# RX8E.net
KiCad netlist of a schematic drawn in EAGLE
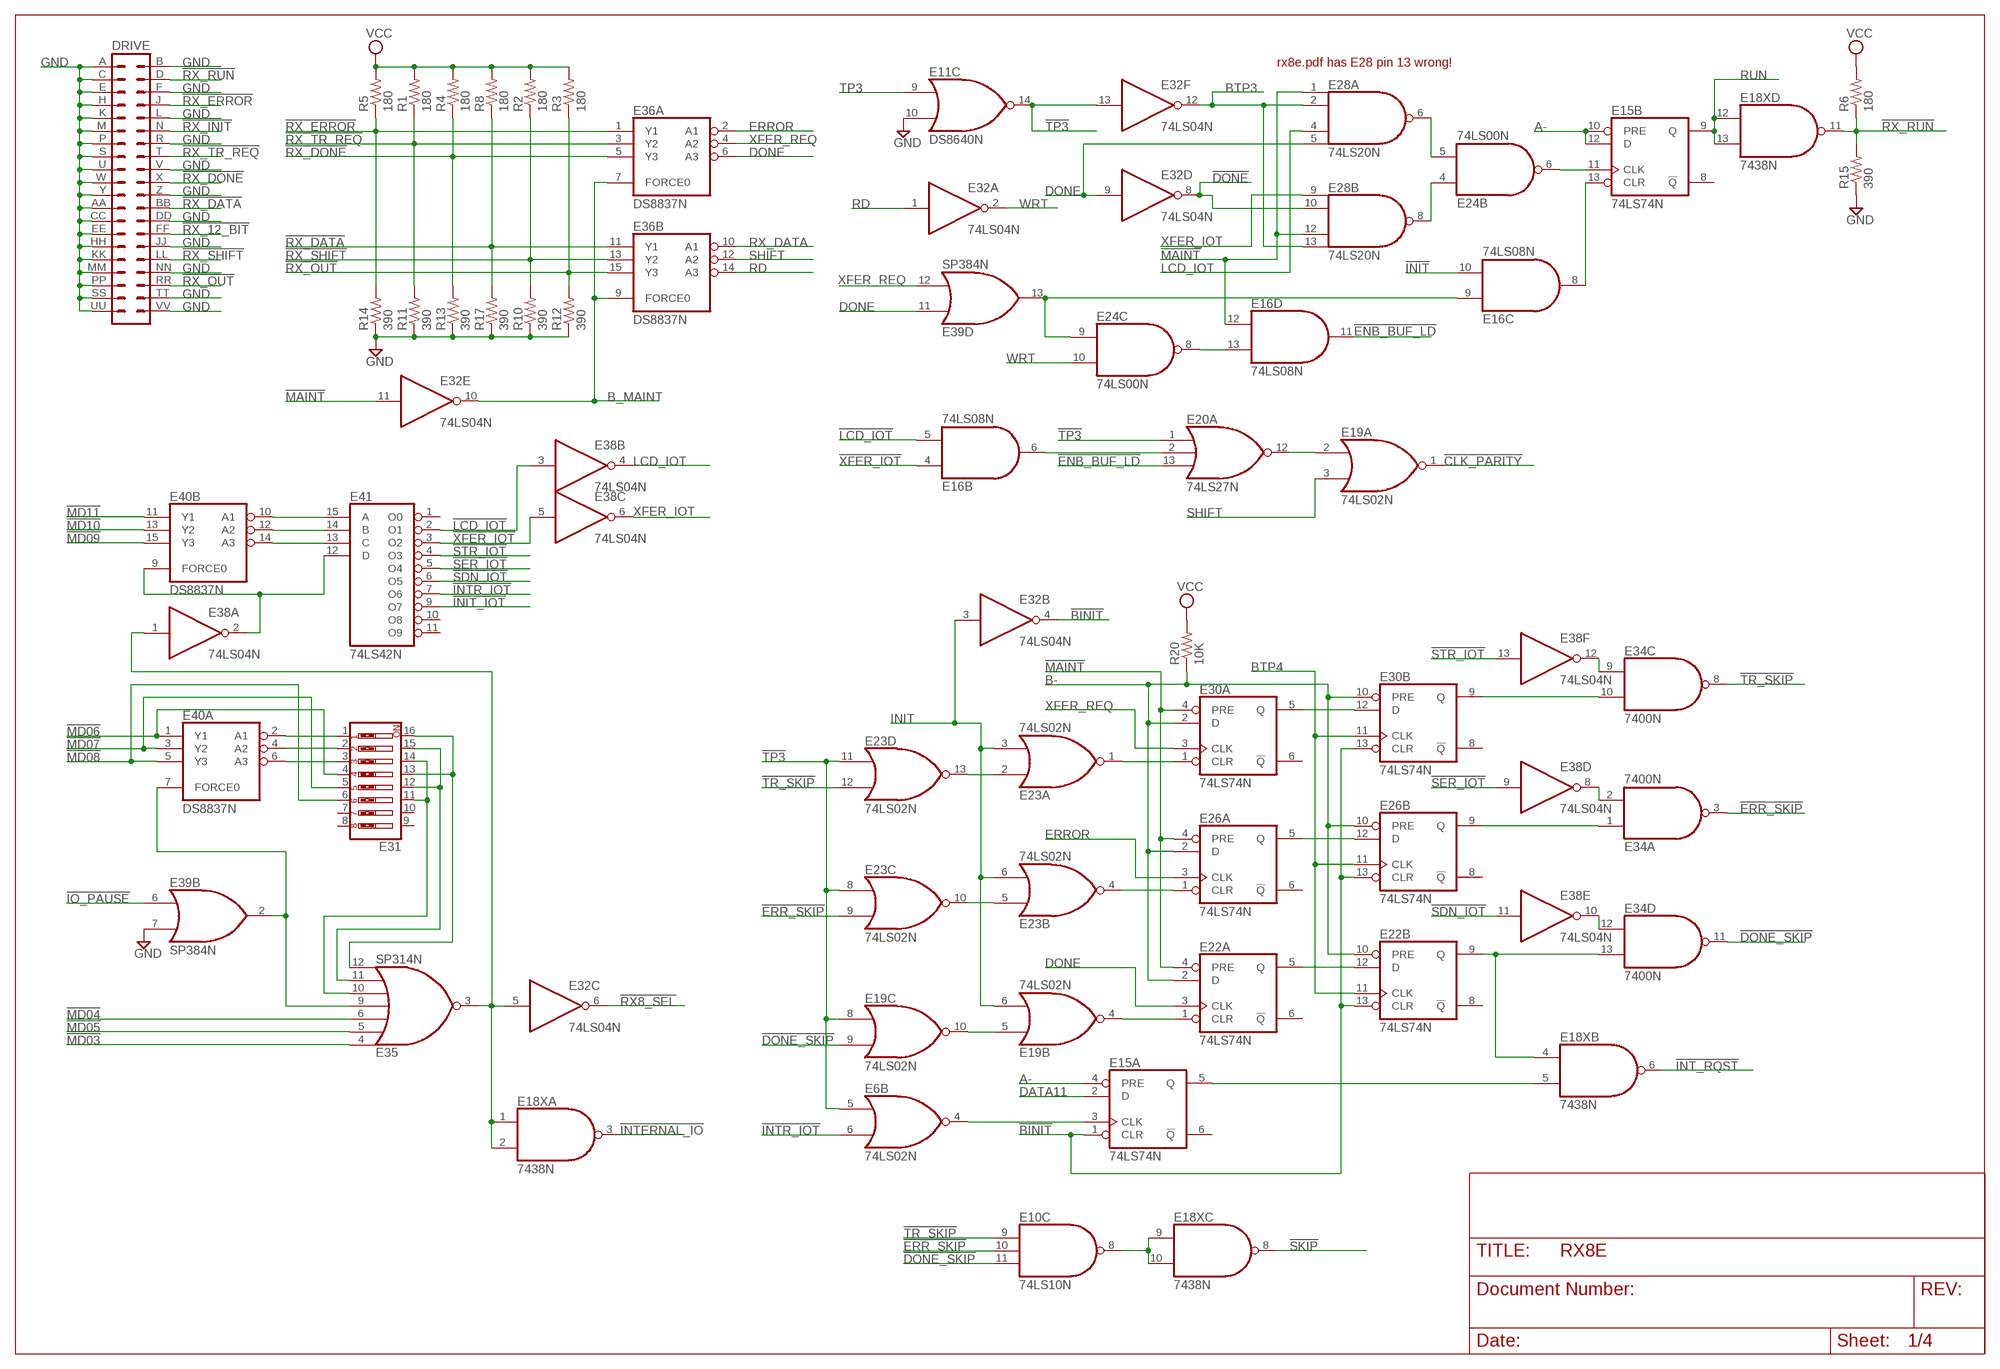
[diagram p0: schematic, sheet 1]
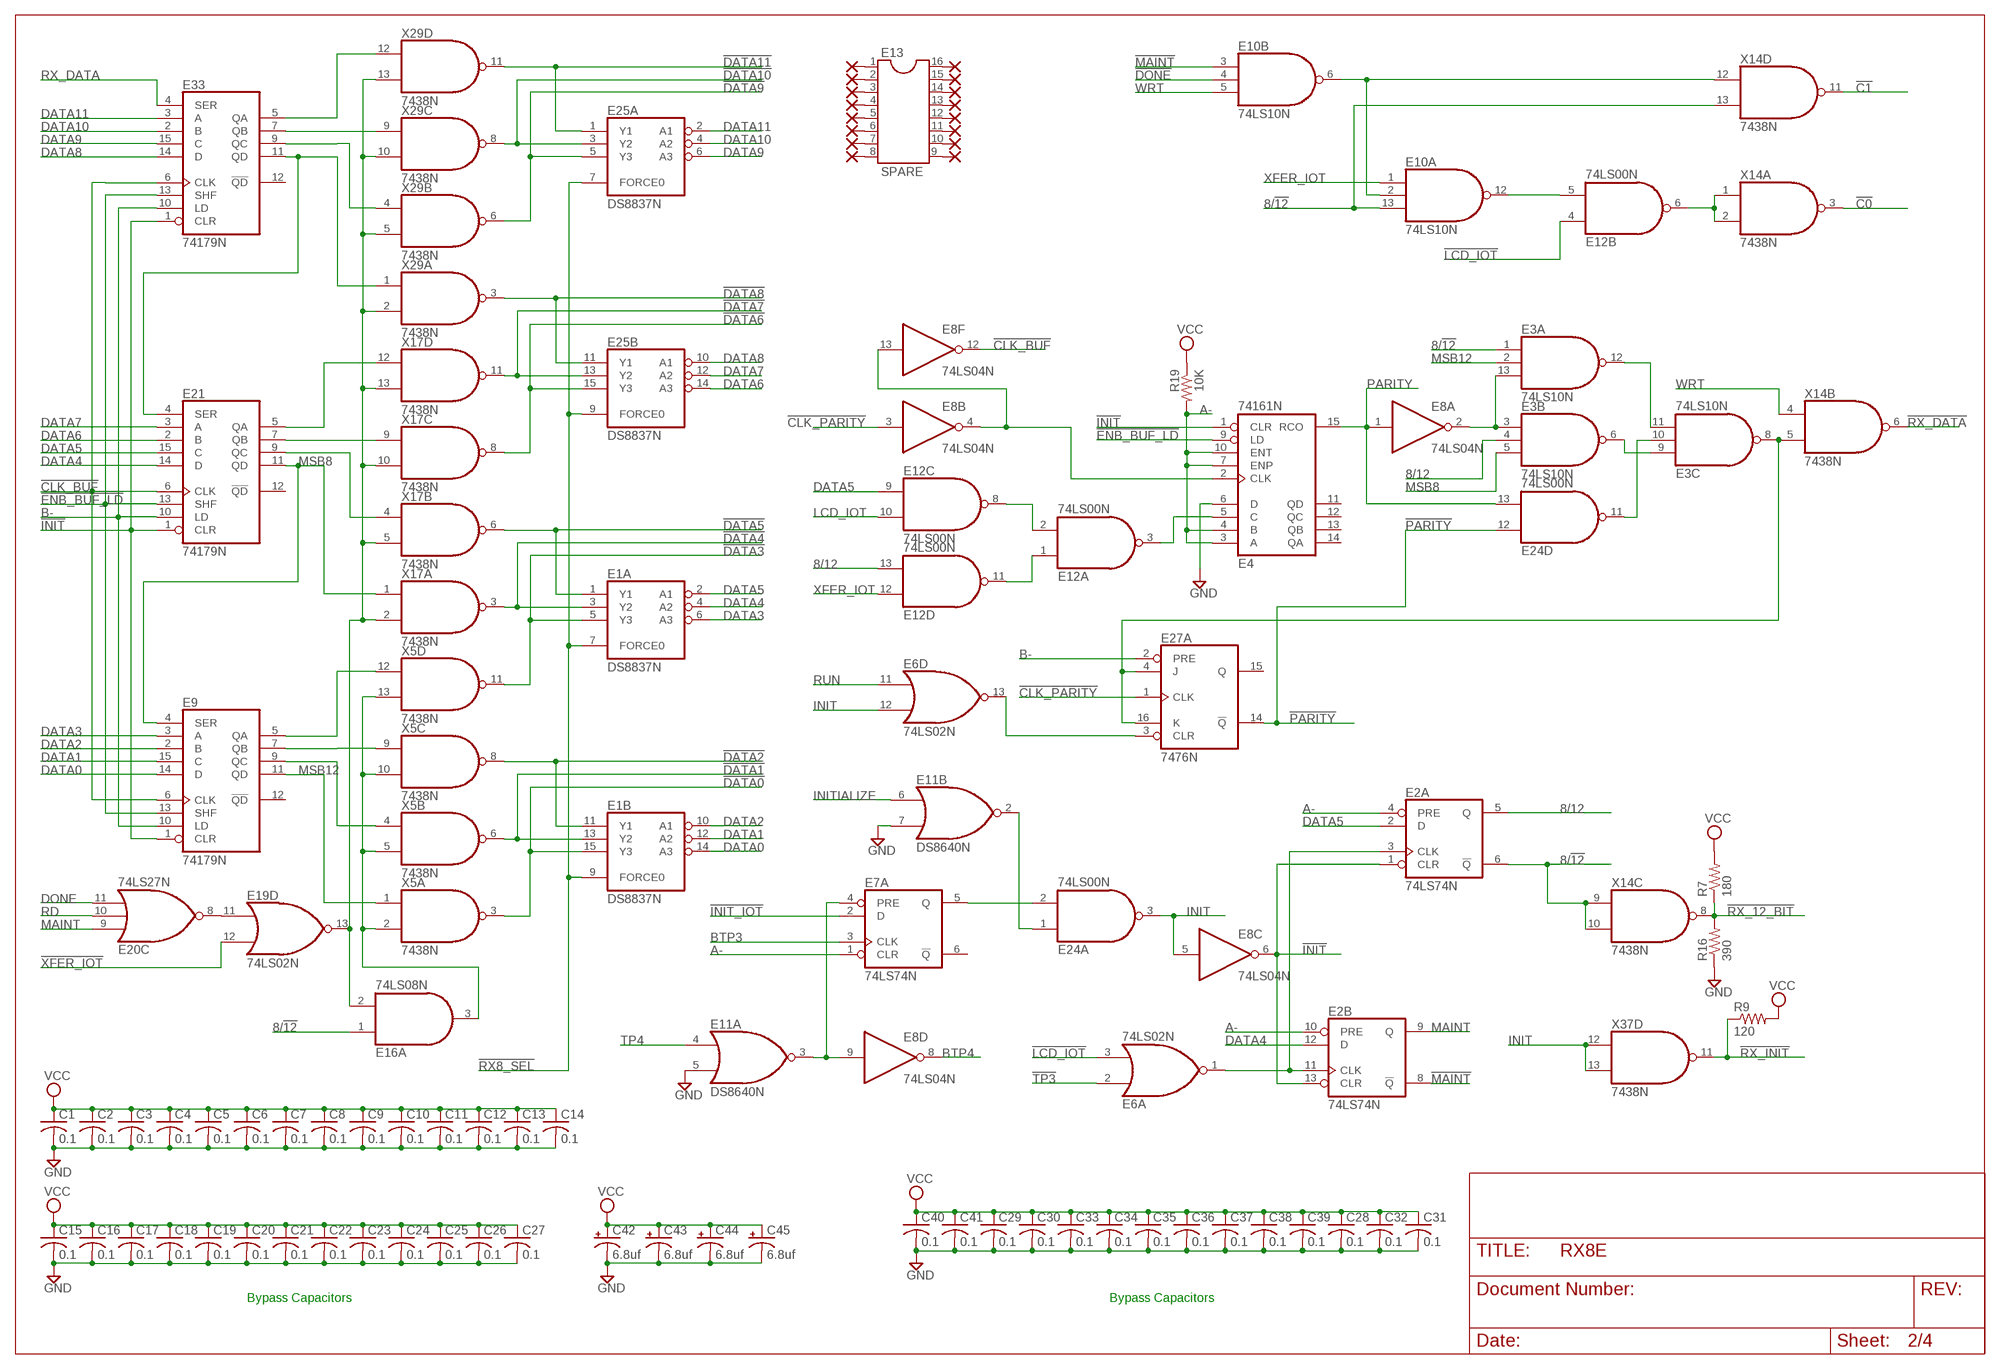
[diagram p1: schematic, sheet 2]
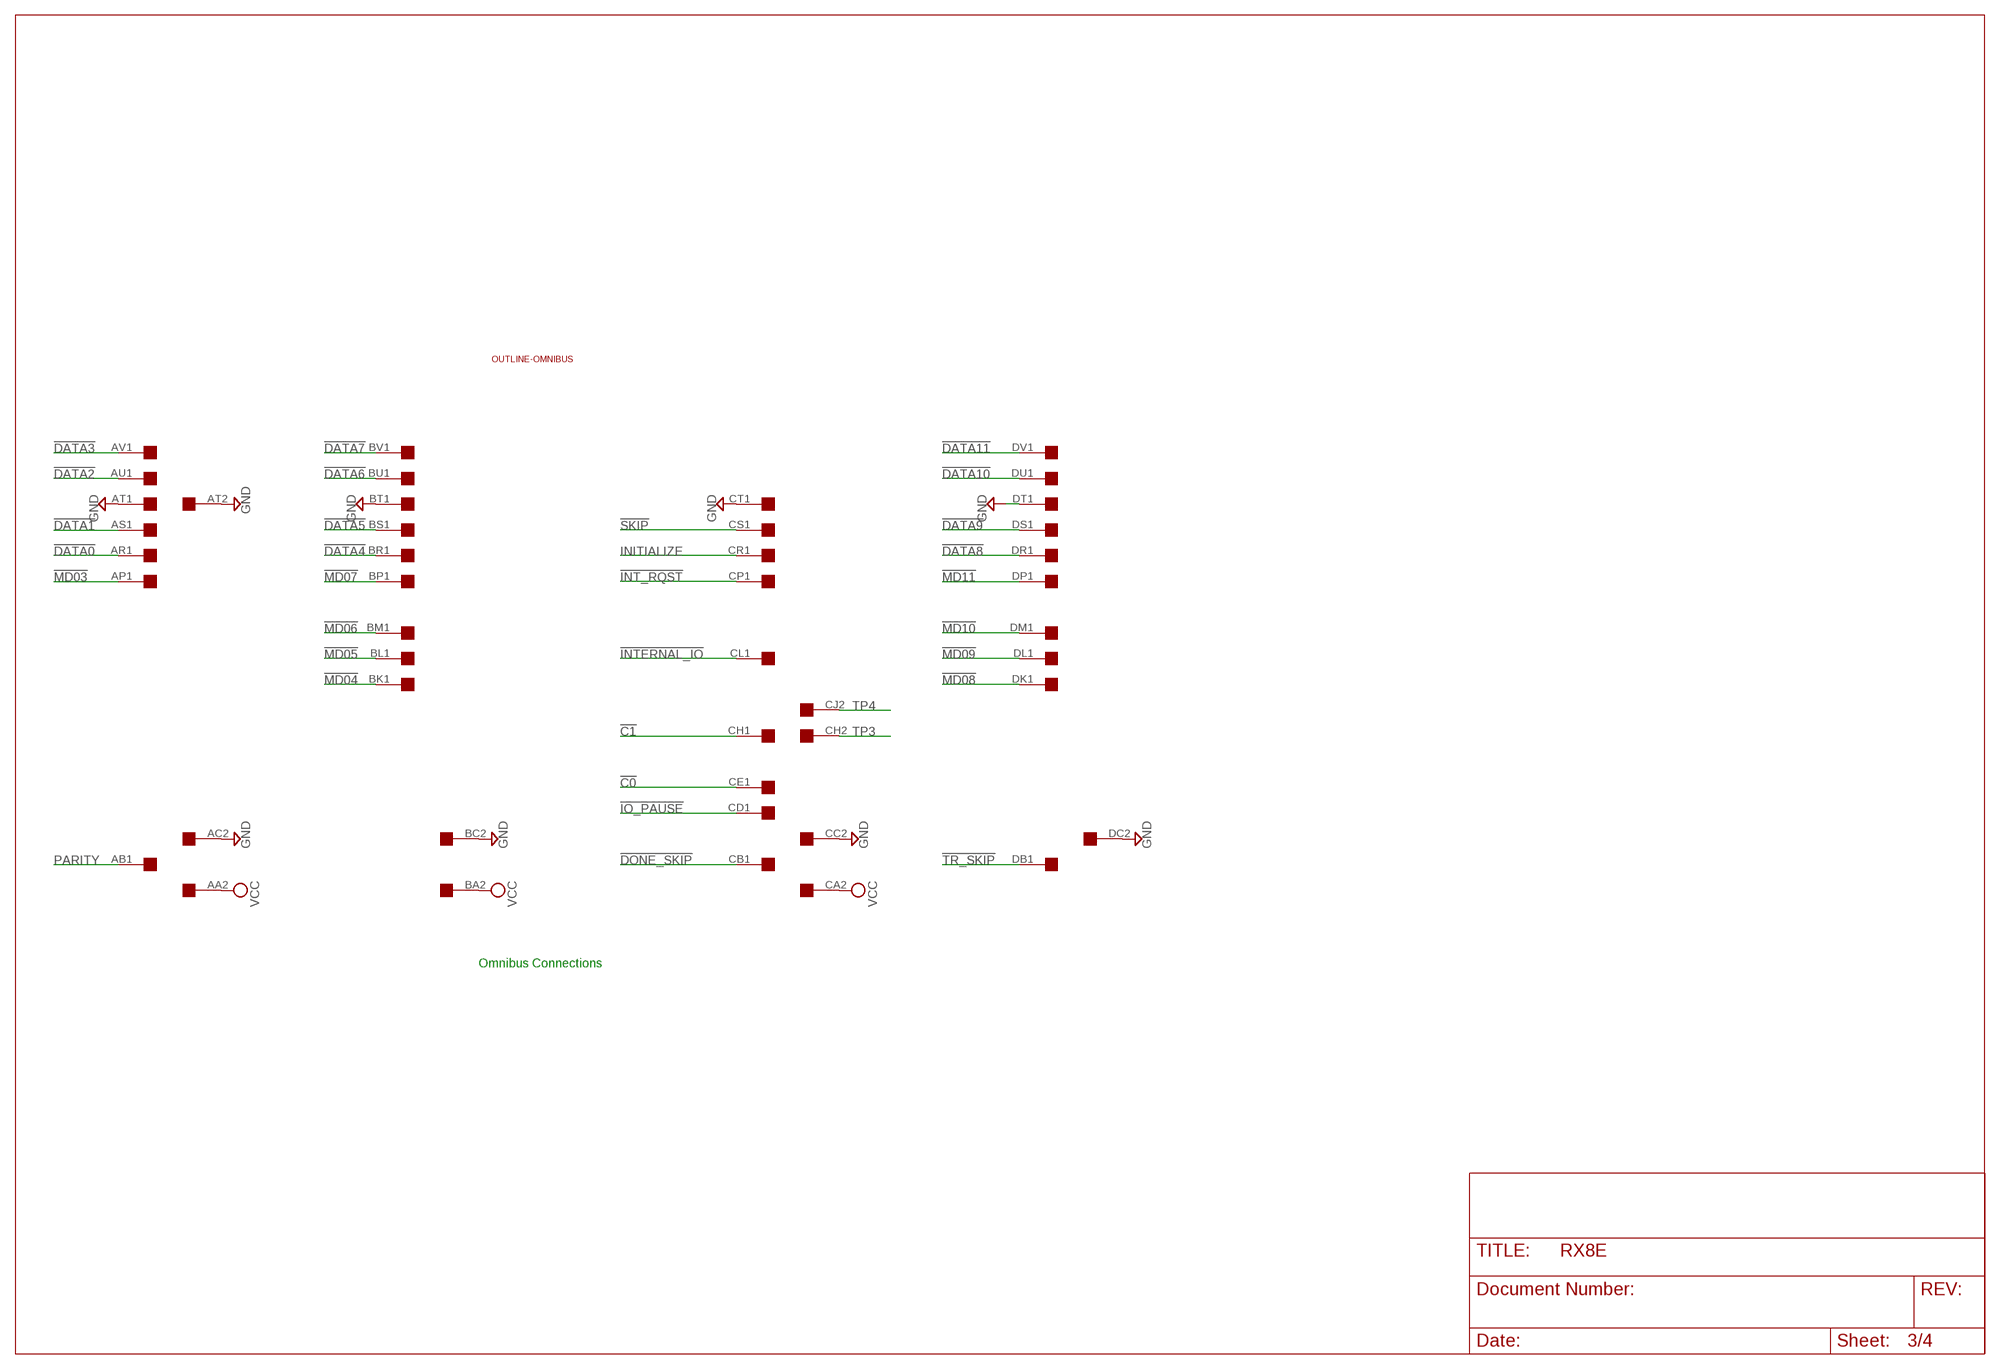
[diagram p2: schematic, sheet 3]
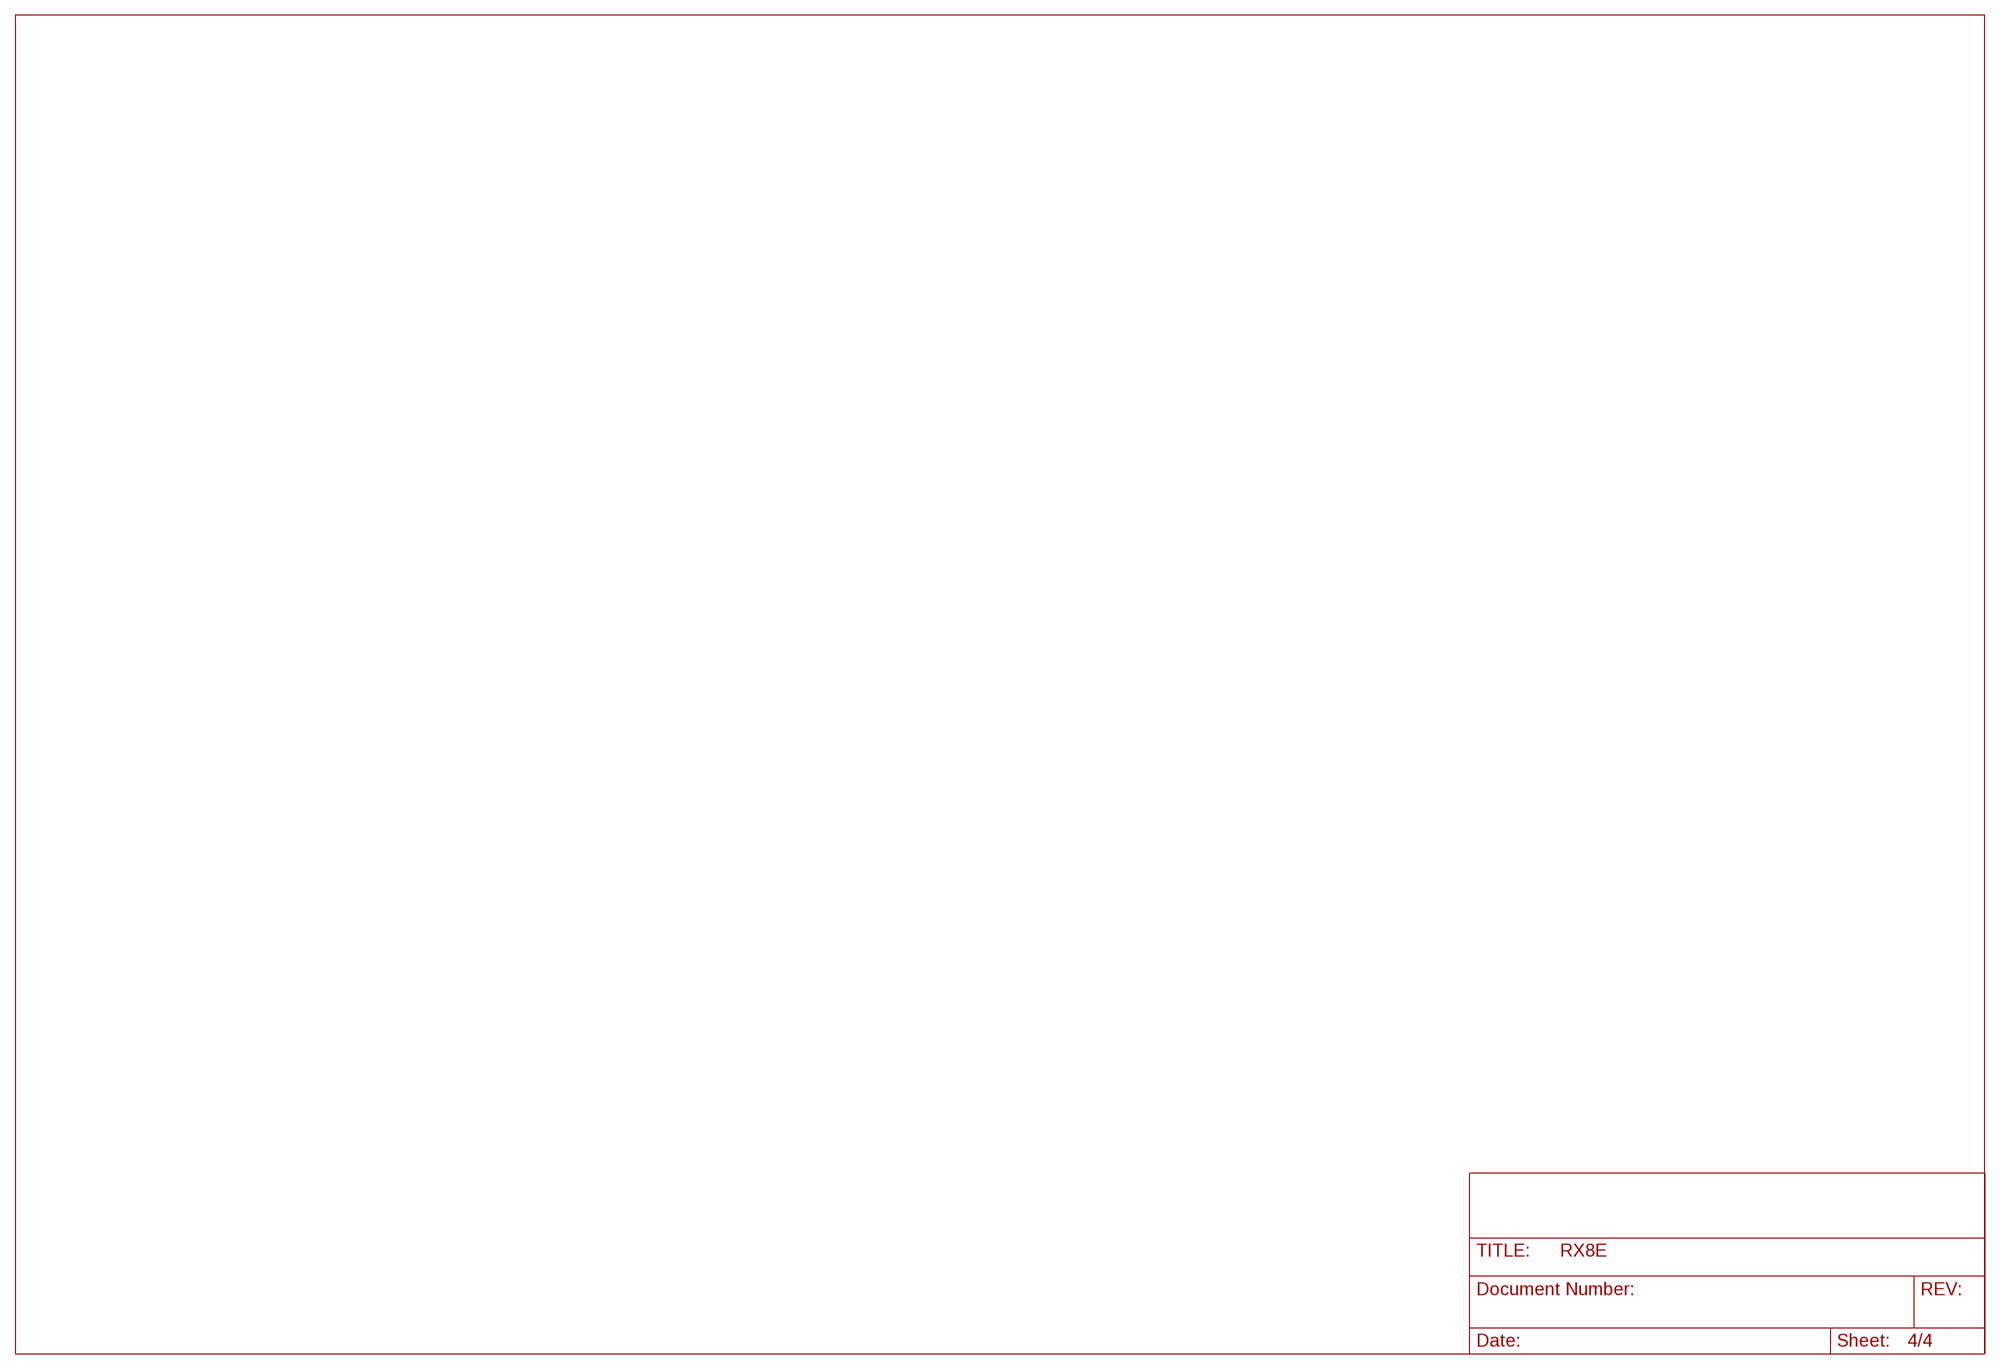
[diagram p3: schematic, sheet 4]

(export (version "E")
  (design (tool "Eeschema 10.0.6"))
  (components
    (comp (ref "U$2")
      (value "QUAD")
      (footprint "eagle-import:EDGE-CON8")
      (libsource (lib "eagle-import") (part "QUAD"))
    )
    (comp (ref "U$5")
      (value "OUTLINE-OMNIBUS")
      (footprint "eagle-import:OMNIBUS")
      (libsource (lib "eagle-import") (part "OUTLINE-OMNIBUS"))
    )
    (comp (ref "C1")
      (value "0.1")
      (footprint "eagle-import:C050-025X075")
      (libsource (lib "eagle-import") (part "C-US050-025X075"))
    )
    (comp (ref "C2")
      (value "0.1")
      (footprint "eagle-import:C050-025X075")
      (libsource (lib "eagle-import") (part "C-US050-025X075"))
    )
    (comp (ref "C3")
      (value "0.1")
      (footprint "eagle-import:C050-025X075")
      (libsource (lib "eagle-import") (part "C-US050-025X075"))
    )
    (comp (ref "C4")
      (value "0.1")
      (footprint "eagle-import:C050-025X075")
      (libsource (lib "eagle-import") (part "C-US050-025X075"))
    )
    (comp (ref "C5")
      (value "0.1")
      (footprint "eagle-import:C050-025X075")
      (libsource (lib "eagle-import") (part "C-US050-025X075"))
    )
    (comp (ref "C6")
      (value "0.1")
      (footprint "eagle-import:C050-025X075")
      (libsource (lib "eagle-import") (part "C-US050-025X075"))
    )
    (comp (ref "C7")
      (value "0.1")
      (footprint "eagle-import:C050-025X075")
      (libsource (lib "eagle-import") (part "C-US050-025X075"))
    )
    (comp (ref "C8")
      (value "0.1")
      (footprint "eagle-import:C050-025X075")
      (libsource (lib "eagle-import") (part "C-US050-025X075"))
    )
    (comp (ref "C9")
      (value "0.1")
      (footprint "eagle-import:C050-025X075")
      (libsource (lib "eagle-import") (part "C-US050-025X075"))
    )
    (comp (ref "C10")
      (value "0.1")
      (footprint "eagle-import:C050-025X075")
      (libsource (lib "eagle-import") (part "C-US050-025X075"))
    )
    (comp (ref "C11")
      (value "0.1")
      (footprint "eagle-import:C050-025X075")
      (libsource (lib "eagle-import") (part "C-US050-025X075"))
    )
    (comp (ref "C12")
      (value "0.1")
      (footprint "eagle-import:C050-025X075")
      (libsource (lib "eagle-import") (part "C-US050-025X075"))
    )
    (comp (ref "C13")
      (value "0.1")
      (footprint "eagle-import:C050-025X075")
      (libsource (lib "eagle-import") (part "C-US050-025X075"))
    )
    (comp (ref "C14")
      (value "0.1")
      (footprint "eagle-import:C050-025X075")
      (libsource (lib "eagle-import") (part "C-US050-025X075"))
    )
    (comp (ref "C15")
      (value "0.1")
      (footprint "eagle-import:C050-025X075")
      (libsource (lib "eagle-import") (part "C-US050-025X075"))
    )
    (comp (ref "C16")
      (value "0.1")
      (footprint "eagle-import:C050-025X075")
      (libsource (lib "eagle-import") (part "C-US050-025X075"))
    )
    (comp (ref "C17")
      (value "0.1")
      (footprint "eagle-import:C050-025X075")
      (libsource (lib "eagle-import") (part "C-US050-025X075"))
    )
    (comp (ref "C18")
      (value "0.1")
      (footprint "eagle-import:C050-025X075")
      (libsource (lib "eagle-import") (part "C-US050-025X075"))
    )
    (comp (ref "C19")
      (value "0.1")
      (footprint "eagle-import:C050-025X075")
      (libsource (lib "eagle-import") (part "C-US050-025X075"))
    )
    (comp (ref "C20")
      (value "0.1")
      (footprint "eagle-import:C050-025X075")
      (libsource (lib "eagle-import") (part "C-US050-025X075"))
    )
    (comp (ref "C21")
      (value "0.1")
      (footprint "eagle-import:C050-025X075")
      (libsource (lib "eagle-import") (part "C-US050-025X075"))
    )
    (comp (ref "C22")
      (value "0.1")
      (footprint "eagle-import:C050-025X075")
      (libsource (lib "eagle-import") (part "C-US050-025X075"))
    )
    (comp (ref "C23")
      (value "0.1")
      (footprint "eagle-import:C050-025X075")
      (libsource (lib "eagle-import") (part "C-US050-025X075"))
    )
    (comp (ref "C24")
      (value "0.1")
      (footprint "eagle-import:C050-025X075")
      (libsource (lib "eagle-import") (part "C-US050-025X075"))
    )
    (comp (ref "C25")
      (value "0.1")
      (footprint "eagle-import:C050-025X075")
      (libsource (lib "eagle-import") (part "C-US050-025X075"))
    )
    (comp (ref "C26")
      (value "0.1")
      (footprint "eagle-import:C050-025X075")
      (libsource (lib "eagle-import") (part "C-US050-025X075"))
    )
    (comp (ref "C27")
      (value "0.1")
      (footprint "eagle-import:C050-025X075")
      (libsource (lib "eagle-import") (part "C-US050-025X075"))
    )
    (comp (ref "C28")
      (value "0.1")
      (footprint "eagle-import:C050-025X075")
      (libsource (lib "eagle-import") (part "C-US050-025X075"))
    )
    (comp (ref "C29")
      (value "0.1")
      (footprint "eagle-import:C050-025X075")
      (libsource (lib "eagle-import") (part "C-US050-025X075"))
    )
    (comp (ref "C30")
      (value "0.1")
      (footprint "eagle-import:C050-025X075")
      (libsource (lib "eagle-import") (part "C-US050-025X075"))
    )
    (comp (ref "C31")
      (value "0.1")
      (footprint "eagle-import:C050-025X075")
      (libsource (lib "eagle-import") (part "C-US050-025X075"))
    )
    (comp (ref "C32")
      (value "0.1")
      (footprint "eagle-import:C050-025X075")
      (libsource (lib "eagle-import") (part "C-US050-025X075"))
    )
    (comp (ref "C33")
      (value "0.1")
      (footprint "eagle-import:C050-025X075")
      (libsource (lib "eagle-import") (part "C-US050-025X075"))
    )
    (comp (ref "C34")
      (value "0.1")
      (footprint "eagle-import:C050-025X075")
      (libsource (lib "eagle-import") (part "C-US050-025X075"))
    )
    (comp (ref "C35")
      (value "0.1")
      (footprint "eagle-import:C050-025X075")
      (libsource (lib "eagle-import") (part "C-US050-025X075"))
    )
    (comp (ref "C36")
      (value "0.1")
      (footprint "eagle-import:C050-025X075")
      (libsource (lib "eagle-import") (part "C-US050-025X075"))
    )
    (comp (ref "C37")
      (value "0.1")
      (footprint "eagle-import:C050-025X075")
      (libsource (lib "eagle-import") (part "C-US050-025X075"))
    )
    (comp (ref "C38")
      (value "0.1")
      (footprint "eagle-import:C050-025X075")
      (libsource (lib "eagle-import") (part "C-US050-025X075"))
    )
    (comp (ref "C39")
      (value "0.1")
      (footprint "eagle-import:C050-025X075")
      (libsource (lib "eagle-import") (part "C-US050-025X075"))
    )
    (comp (ref "C40")
      (value "0.1")
      (footprint "eagle-import:C050-025X075")
      (libsource (lib "eagle-import") (part "C-US050-025X075"))
    )
    (comp (ref "C41")
      (value "0.1")
      (footprint "eagle-import:C050-025X075")
      (libsource (lib "eagle-import") (part "C-US050-025X075"))
    )
    (comp (ref "C42")
      (value "6.8uf")
      (footprint "eagle-import:E22-6")
      (libsource (lib "eagle-import") (part "CPOL-USE22-6AXIAL"))
    )
    (comp (ref "C43")
      (value "6.8uf")
      (footprint "eagle-import:E22-6")
      (libsource (lib "eagle-import") (part "CPOL-USE22-6AXIAL"))
    )
    (comp (ref "C44")
      (value "6.8uf")
      (footprint "eagle-import:E22-6")
      (libsource (lib "eagle-import") (part "CPOL-USE22-6AXIAL"))
    )
    (comp (ref "C45")
      (value "6.8uf")
      (footprint "eagle-import:E22-6")
      (libsource (lib "eagle-import") (part "CPOL-USE22-6AXIAL"))
    )
    (comp (ref "E1")
      (value "DS8837N")
      (footprint "eagle-import:DIL16")
      (libsource (lib "eagle-import") (part "DS8837N"))
    )
    (comp (ref "E2")
      (value "74LS74N")
      (footprint "eagle-import:DIL14")
      (libsource (lib "eagle-import") (part "7474NLS"))
    )
    (comp (ref "E3")
      (value "74LS10N")
      (footprint "eagle-import:DIL14")
      (libsource (lib "eagle-import") (part "7410NLS"))
    )
    (comp (ref "E4")
      (value "74161N")
      (footprint "eagle-import:DIL16")
      (libsource (lib "eagle-import") (part "74161N"))
    )
    (comp (ref "E6")
      (value "74LS02N")
      (footprint "eagle-import:DIL14")
      (libsource (lib "eagle-import") (part "7402NLS"))
    )
    (comp (ref "E7")
      (value "74LS74N")
      (footprint "eagle-import:DIL14")
      (libsource (lib "eagle-import") (part "7474NLS"))
    )
    (comp (ref "E8")
      (value "74LS04N")
      (footprint "eagle-import:DIL14")
      (libsource (lib "eagle-import") (part "7404NLS"))
    )
    (comp (ref "E9")
      (value "74179N")
      (footprint "eagle-import:DIL16")
      (libsource (lib "eagle-import") (part "74179N"))
    )
    (comp (ref "E10")
      (value "74LS10N")
      (footprint "eagle-import:DIL14")
      (libsource (lib "eagle-import") (part "7410NLS"))
    )
    (comp (ref "E11")
      (value "DS8640N")
      (footprint "eagle-import:DIL14")
      (libsource (lib "eagle-import") (part "DS8640N"))
    )
    (comp (ref "E12")
      (value "74LS00N")
      (footprint "eagle-import:DIL14")
      (libsource (lib "eagle-import") (part "7400NLS"))
    )
    (comp (ref "E13")
      (value "SPARE")
      (footprint "eagle-import:DIL16")
      (libsource (lib "eagle-import") (part "DIL16"))
    )
    (comp (ref "E16")
      (value "74LS08N")
      (footprint "eagle-import:DIL14")
      (libsource (lib "eagle-import") (part "7408NLS"))
    )
    (comp (ref "E19")
      (value "74LS02N")
      (footprint "eagle-import:DIL14")
      (libsource (lib "eagle-import") (part "7402NLS"))
    )
    (comp (ref "E20")
      (value "74LS27N")
      (footprint "eagle-import:DIL14")
      (libsource (lib "eagle-import") (part "7427NLS"))
    )
    (comp (ref "E21")
      (value "74179N")
      (footprint "eagle-import:DIL16")
      (libsource (lib "eagle-import") (part "74179N"))
    )
    (comp (ref "E24")
      (value "74LS00N")
      (footprint "eagle-import:DIL14")
      (libsource (lib "eagle-import") (part "7400NLS"))
    )
    (comp (ref "E25")
      (value "DS8837N")
      (footprint "eagle-import:DIL16")
      (libsource (lib "eagle-import") (part "DS8837N"))
    )
    (comp (ref "E27")
      (value "7476N")
      (footprint "eagle-import:DIL16")
      (libsource (lib "eagle-import") (part "7476N"))
    )
    (comp (ref "E33")
      (value "74179N")
      (footprint "eagle-import:DIL16")
      (libsource (lib "eagle-import") (part "74179N"))
    )
    (comp (ref "PAD10")
      (value "1,6/0,8")
      (footprint "eagle-import:1,6_0,8")
      (libsource (lib "eagle-import") (part "1,6/0,8"))
    )
    (comp (ref "PAD11")
      (value "1,6/0,8")
      (footprint "eagle-import:1,6_0,8")
      (libsource (lib "eagle-import") (part "1,6/0,8"))
    )
    (comp (ref "PAD12")
      (value "1,6/0,8")
      (footprint "eagle-import:1,6_0,8")
      (libsource (lib "eagle-import") (part "1,6/0,8"))
    )
    (comp (ref "PAD13")
      (value "1,6/0,8")
      (footprint "eagle-import:1,6_0,8")
      (libsource (lib "eagle-import") (part "1,6/0,8"))
    )
    (comp (ref "PAD14")
      (value "1,6/0,8")
      (footprint "eagle-import:1,6_0,8")
      (libsource (lib "eagle-import") (part "1,6/0,8"))
    )
    (comp (ref "PAD15")
      (value "1,6/0,8")
      (footprint "eagle-import:1,6_0,8")
      (libsource (lib "eagle-import") (part "1,6/0,8"))
    )
    (comp (ref "PAD16")
      (value "1,6/0,8")
      (footprint "eagle-import:1,6_0,8")
      (libsource (lib "eagle-import") (part "1,6/0,8"))
    )
    (comp (ref "PAD17")
      (value "1,6/0,8")
      (footprint "eagle-import:1,6_0,8")
      (libsource (lib "eagle-import") (part "1,6/0,8"))
    )
    (comp (ref "PAD20")
      (value "1,6/0,8")
      (footprint "eagle-import:1,6_0,8")
      (libsource (lib "eagle-import") (part "1,6/0,8"))
    )
    (comp (ref "PAD21")
      (value "1,6/0,8")
      (footprint "eagle-import:1,6_0,8")
      (libsource (lib "eagle-import") (part "1,6/0,8"))
    )
    (comp (ref "PAD22")
      (value "1,6/0,8")
      (footprint "eagle-import:1,6_0,8")
      (libsource (lib "eagle-import") (part "1,6/0,8"))
    )
    (comp (ref "PAD23")
      (value "1,6/0,8")
      (footprint "eagle-import:1,6_0,8")
      (libsource (lib "eagle-import") (part "1,6/0,8"))
    )
    (comp (ref "PAD24")
      (value "1,6/0,8")
      (footprint "eagle-import:1,6_0,8")
      (libsource (lib "eagle-import") (part "1,6/0,8"))
    )
    (comp (ref "PAD25")
      (value "1,6/0,8")
      (footprint "eagle-import:1,6_0,8")
      (libsource (lib "eagle-import") (part "1,6/0,8"))
    )
    (comp (ref "PAD26")
      (value "1,6/0,8")
      (footprint "eagle-import:1,6_0,8")
      (libsource (lib "eagle-import") (part "1,6/0,8"))
    )
    (comp (ref "PAD27")
      (value "1,6/0,8")
      (footprint "eagle-import:1,6_0,8")
      (libsource (lib "eagle-import") (part "1,6/0,8"))
    )
    (comp (ref "R7")
      (value "180")
      (footprint "eagle-import:0207_10")
      (libsource (lib "eagle-import") (part "R-US_0207/10"))
    )
    (comp (ref "R9")
      (value "120")
      (footprint "eagle-import:0207_10")
      (libsource (lib "eagle-import") (part "R-US_0207/10"))
    )
    (comp (ref "R16")
      (value "390")
      (footprint "eagle-import:0207_10")
      (libsource (lib "eagle-import") (part "R-US_0207/10"))
    )
    (comp (ref "R19")
      (value "10K")
      (footprint "eagle-import:0207_10")
      (libsource (lib "eagle-import") (part "R-US_0207/10"))
    )
    (comp (ref "X5")
      (value "7438N")
      (footprint "eagle-import:DIL14")
      (libsource (lib "eagle-import") (part "7403NS"))
    )
    (comp (ref "X14")
      (value "7438N")
      (footprint "eagle-import:DIL14")
      (libsource (lib "eagle-import") (part "7403NS"))
    )
    (comp (ref "X17")
      (value "7438N")
      (footprint "eagle-import:DIL14")
      (libsource (lib "eagle-import") (part "7403NS"))
    )
    (comp (ref "X29")
      (value "7438N")
      (footprint "eagle-import:DIL14")
      (libsource (lib "eagle-import") (part "7403NS"))
    )
    (comp (ref "X37")
      (value "7438N")
      (footprint "eagle-import:DIL14")
      (libsource (lib "eagle-import") (part "7403NS"))
    )
    (comp (ref "DRIVE")
      (value "DEC40PINH")
      (footprint "eagle-import:DEC40PINH")
      (libsource (lib "eagle-import") (part "DEC40PINH"))
    )
    (comp (ref "E15")
      (value "74LS74N")
      (footprint "eagle-import:DIL14")
      (libsource (lib "eagle-import") (part "7474NLS"))
    )
    (comp (ref "E18X")
      (value "7438N")
      (footprint "eagle-import:DIL14")
      (libsource (lib "eagle-import") (part "7403NS"))
    )
    (comp (ref "E22")
      (value "74LS74N")
      (footprint "eagle-import:DIL14")
      (libsource (lib "eagle-import") (part "7474NLS"))
    )
    (comp (ref "E23")
      (value "74LS02N")
      (footprint "eagle-import:DIL14")
      (libsource (lib "eagle-import") (part "7402NLS"))
    )
    (comp (ref "E26")
      (value "74LS74N")
      (footprint "eagle-import:DIL14")
      (libsource (lib "eagle-import") (part "7474NLS"))
    )
    (comp (ref "E28")
      (value "74LS20N")
      (footprint "eagle-import:DIL14")
      (libsource (lib "eagle-import") (part "7420NLS"))
    )
    (comp (ref "E30")
      (value "74LS74N")
      (footprint "eagle-import:DIL14")
      (libsource (lib "eagle-import") (part "7474NLS"))
    )
    (comp (ref "E31")
      (value "SW_DIP-8")
      (footprint "eagle-import:EDG-08")
      (libsource (lib "eagle-import") (part "SW_DIP-8"))
    )
    (comp (ref "E32")
      (value "74LS04N")
      (footprint "eagle-import:DIL14")
      (libsource (lib "eagle-import") (part "7404NLS"))
    )
    (comp (ref "E34")
      (value "7400N")
      (footprint "eagle-import:DIL14")
      (libsource (lib "eagle-import") (part "7400N"))
    )
    (comp (ref "E35")
      (value "SP314N")
      (footprint "eagle-import:DIL14")
      (libsource (lib "eagle-import") (part "SP314N"))
    )
    (comp (ref "E36")
      (value "DS8837N")
      (footprint "eagle-import:DIL16")
      (libsource (lib "eagle-import") (part "DS8837N"))
    )
    (comp (ref "E38")
      (value "74LS04N")
      (footprint "eagle-import:DIL14")
      (libsource (lib "eagle-import") (part "7404NLS"))
    )
    (comp (ref "E39")
      (value "SP384N")
      (footprint "eagle-import:DIL14")
      (libsource (lib "eagle-import") (part "SP384N"))
    )
    (comp (ref "E40")
      (value "DS8837N")
      (footprint "eagle-import:DIL16")
      (libsource (lib "eagle-import") (part "DS8837N"))
    )
    (comp (ref "E41")
      (value "74LS42N")
      (footprint "eagle-import:DIL16")
      (libsource (lib "eagle-import") (part "7442NLS"))
    )
    (comp (ref "R1")
      (value "180")
      (footprint "eagle-import:0207_10")
      (libsource (lib "eagle-import") (part "R-US_0207/10"))
    )
    (comp (ref "R2")
      (value "180")
      (footprint "eagle-import:0207_10")
      (libsource (lib "eagle-import") (part "R-US_0207/10"))
    )
    (comp (ref "R3")
      (value "180")
      (footprint "eagle-import:0207_10")
      (libsource (lib "eagle-import") (part "R-US_0207/10"))
    )
    (comp (ref "R4")
      (value "180")
      (footprint "eagle-import:0207_10")
      (libsource (lib "eagle-import") (part "R-US_0207/10"))
    )
    (comp (ref "R5")
      (value "180")
      (footprint "eagle-import:0207_10")
      (libsource (lib "eagle-import") (part "R-US_0207/10"))
    )
    (comp (ref "R6")
      (value "180")
      (footprint "eagle-import:0207_10")
      (libsource (lib "eagle-import") (part "R-US_0207/10"))
    )
    (comp (ref "R8")
      (value "180")
      (footprint "eagle-import:0207_10")
      (libsource (lib "eagle-import") (part "R-US_0207/10"))
    )
    (comp (ref "R10")
      (value "390")
      (footprint "eagle-import:0207_10")
      (libsource (lib "eagle-import") (part "R-US_0207/10"))
    )
    (comp (ref "R11")
      (value "390")
      (footprint "eagle-import:0207_10")
      (libsource (lib "eagle-import") (part "R-US_0207/10"))
    )
    (comp (ref "R12")
      (value "390")
      (footprint "eagle-import:0207_10")
      (libsource (lib "eagle-import") (part "R-US_0207/10"))
    )
    (comp (ref "R13")
      (value "390")
      (footprint "eagle-import:0207_10")
      (libsource (lib "eagle-import") (part "R-US_0207/10"))
    )
    (comp (ref "R14")
      (value "390")
      (footprint "eagle-import:0207_10")
      (libsource (lib "eagle-import") (part "R-US_0207/10"))
    )
    (comp (ref "R15")
      (value "390")
      (footprint "eagle-import:0207_10")
      (libsource (lib "eagle-import") (part "R-US_0207/10"))
    )
    (comp (ref "R17")
      (value "390")
      (footprint "eagle-import:0207_10")
      (libsource (lib "eagle-import") (part "R-US_0207/10"))
    )
    (comp (ref "R20")
      (value "10K")
      (footprint "eagle-import:0207_10")
      (libsource (lib "eagle-import") (part "R-US_0207/10"))
    )
  )
  (nets
    (net (code "1") (name "8{slash}12") (class "Default")
      (node (ref "E12") (pin "13") (pinfunction "I1_13") (pintype "input"))
      (node (ref "E2") (pin "5") (pinfunction "Q_5") (pintype "output"))
      (node (ref "E3") (pin "4") (pinfunction "I1_4") (pintype "input"))
    )
    (net (code "2") (name "8{slash}~{12}") (class "Default")
      (node (ref "E10") (pin "13") (pinfunction "I2_13") (pintype "input"))
      (node (ref "E16") (pin "1") (pinfunction "I0_1") (pintype "input"))
      (node (ref "E2") (pin "6") (pinfunction "~{Q}_6") (pintype "output"))
      (node (ref "E3") (pin "1") (pinfunction "I0_1") (pintype "input"))
      (node (ref "X14") (pin "10") (pinfunction "I1_10") (pintype "input"))
      (node (ref "X14") (pin "13") (pinfunction "I1_13") (pintype "input"))
      (node (ref "X14") (pin "9") (pinfunction "I0_9") (pintype "input"))
    )
    (net (code "3") (name "A-") (class "Default")
      (node (ref "E15") (pin "10") (pinfunction "PRE_10") (pintype "input"))
      (node (ref "E15") (pin "12") (pinfunction "D_12") (pintype "input"))
      (node (ref "E15") (pin "4") (pinfunction "PRE_4") (pintype "input"))
      (node (ref "E2") (pin "10") (pinfunction "PRE_10") (pintype "input"))
      (node (ref "E2") (pin "4") (pinfunction "PRE_4") (pintype "input"))
      (node (ref "E4") (pin "10") (pinfunction "ENT_10") (pintype "input"))
      (node (ref "E4") (pin "3") (pinfunction "A_3") (pintype "input"))
      (node (ref "E4") (pin "4") (pinfunction "B_4") (pintype "input"))
      (node (ref "E4") (pin "7") (pinfunction "ENP_7") (pintype "input"))
      (node (ref "E7") (pin "1") (pinfunction "CLR_1") (pintype "input"))
      (node (ref "R19") (pin "2") (pinfunction "2_2") (pintype "passive"))
    )
    (net (code "4") (name "B-") (class "Default")
      (node (ref "E21") (pin "10") (pinfunction "LD_10") (pintype "input"))
      (node (ref "E22") (pin "10") (pinfunction "PRE_10") (pintype "input"))
      (node (ref "E22") (pin "2") (pinfunction "D_2") (pintype "input"))
      (node (ref "E26") (pin "10") (pinfunction "PRE_10") (pintype "input"))
      (node (ref "E26") (pin "2") (pinfunction "D_2") (pintype "input"))
      (node (ref "E27") (pin "2") (pinfunction "PRE_2") (pintype "input"))
      (node (ref "E30") (pin "10") (pinfunction "PRE_10") (pintype "input"))
      (node (ref "E30") (pin "2") (pinfunction "D_2") (pintype "input"))
      (node (ref "E33") (pin "10") (pinfunction "LD_10") (pintype "input"))
      (node (ref "E9") (pin "10") (pinfunction "LD_10") (pintype "input"))
      (node (ref "R20") (pin "1") (pinfunction "1_1") (pintype "passive"))
    )
    (net (code "5") (name "BTP3") (class "Default")
      (node (ref "E28") (pin "13") (pinfunction "I3_13") (pintype "input"))
      (node (ref "E28") (pin "2") (pinfunction "I1_2") (pintype "input"))
      (node (ref "E32") (pin "12") (pinfunction "O_12") (pintype "output"))
      (node (ref "E7") (pin "3") (pinfunction "CLK_3") (pintype "input"))
    )
    (net (code "6") (name "BTP4") (class "Default")
      (node (ref "E22") (pin "11") (pinfunction "CLK_11") (pintype "input"))
      (node (ref "E26") (pin "11") (pinfunction "CLK_11") (pintype "input"))
      (node (ref "E30") (pin "11") (pinfunction "CLK_11") (pintype "input"))
      (node (ref "E8") (pin "8") (pinfunction "O_8") (pintype "output"))
    )
    (net (code "7") (name "B_MAINT") (class "Default")
      (node (ref "E32") (pin "10") (pinfunction "O_10") (pintype "output"))
      (node (ref "E36") (pin "7") (pinfunction "FORCE0_7") (pintype "input"))
      (node (ref "E36") (pin "9") (pinfunction "FORCE0_9") (pintype "input"))
    )
    (net (code "8") (name "DATA0") (class "Default")
      (node (ref "E1") (pin "14") (pinfunction "A3_14") (pintype "output"))
      (node (ref "E9") (pin "14") (pinfunction "D_14") (pintype "input"))
    )
    (net (code "9") (name "DATA1") (class "Default")
      (node (ref "E1") (pin "12") (pinfunction "A2_12") (pintype "output"))
      (node (ref "E9") (pin "15") (pinfunction "C_15") (pintype "input"))
    )
    (net (code "10") (name "DATA2") (class "Default")
      (node (ref "E1") (pin "10") (pinfunction "A1_10") (pintype "output"))
      (node (ref "E9") (pin "2") (pinfunction "B_2") (pintype "input"))
    )
    (net (code "11") (name "DATA3") (class "Default")
      (node (ref "E1") (pin "6") (pinfunction "A3_6") (pintype "output"))
      (node (ref "E9") (pin "3") (pinfunction "A_3") (pintype "input"))
    )
    (net (code "12") (name "DATA4") (class "Default")
      (node (ref "E1") (pin "4") (pinfunction "A2_4") (pintype "output"))
      (node (ref "E2") (pin "12") (pinfunction "D_12") (pintype "input"))
      (node (ref "E21") (pin "14") (pinfunction "D_14") (pintype "input"))
    )
    (net (code "13") (name "DATA5") (class "Default")
      (node (ref "E1") (pin "2") (pinfunction "A1_2") (pintype "output"))
      (node (ref "E12") (pin "9") (pinfunction "I0_9") (pintype "input"))
      (node (ref "E2") (pin "2") (pinfunction "D_2") (pintype "input"))
      (node (ref "E21") (pin "15") (pinfunction "C_15") (pintype "input"))
    )
    (net (code "14") (name "DATA6") (class "Default")
      (node (ref "E21") (pin "2") (pinfunction "B_2") (pintype "input"))
      (node (ref "E25") (pin "14") (pinfunction "A3_14") (pintype "output"))
    )
    (net (code "15") (name "DATA7") (class "Default")
      (node (ref "E21") (pin "3") (pinfunction "A_3") (pintype "input"))
      (node (ref "E25") (pin "12") (pinfunction "A2_12") (pintype "output"))
    )
    (net (code "16") (name "DATA8") (class "Default")
      (node (ref "E25") (pin "10") (pinfunction "A1_10") (pintype "output"))
      (node (ref "E33") (pin "14") (pinfunction "D_14") (pintype "input"))
    )
    (net (code "17") (name "DATA9") (class "Default")
      (node (ref "E25") (pin "6") (pinfunction "A3_6") (pintype "output"))
      (node (ref "E33") (pin "15") (pinfunction "C_15") (pintype "input"))
    )
    (net (code "18") (name "DATA10") (class "Default")
      (node (ref "E25") (pin "4") (pinfunction "A2_4") (pintype "output"))
      (node (ref "E33") (pin "2") (pinfunction "B_2") (pintype "input"))
    )
    (net (code "19") (name "DATA11") (class "Default")
      (node (ref "E15") (pin "2") (pinfunction "D_2") (pintype "input"))
      (node (ref "E25") (pin "2") (pinfunction "A1_2") (pintype "output"))
      (node (ref "E33") (pin "3") (pinfunction "A_3") (pintype "input"))
    )
    (net (code "20") (name "DONE") (class "Default")
      (node (ref "E20") (pin "11") (pinfunction "I2_11") (pintype "input"))
      (node (ref "E22") (pin "3") (pinfunction "CLK_3") (pintype "input"))
      (node (ref "E28") (pin "5") (pinfunction "I3_5") (pintype "input"))
      (node (ref "E32") (pin "9") (pinfunction "I_9") (pintype "input"))
      (node (ref "E36") (pin "6") (pinfunction "A3_6") (pintype "output"))
      (node (ref "E39") (pin "11") (pinfunction "I0_11") (pintype "input"))
    )
    (net (code "21") (name "ERROR") (class "Default")
      (node (ref "E26") (pin "3") (pinfunction "CLK_3") (pintype "input"))
      (node (ref "E36") (pin "2") (pinfunction "A1_2") (pintype "output"))
    )
    (net (code "22") (name "GND") (class "Default")
      (node (ref "C1") (pin "2") (pinfunction "2_2") (pintype "passive"))
      (node (ref "C10") (pin "2") (pinfunction "2_2") (pintype "passive"))
      (node (ref "C11") (pin "2") (pinfunction "2_2") (pintype "passive"))
      (node (ref "C12") (pin "2") (pinfunction "2_2") (pintype "passive"))
      (node (ref "C13") (pin "2") (pinfunction "2_2") (pintype "passive"))
      (node (ref "C14") (pin "2") (pinfunction "2_2") (pintype "passive"))
      (node (ref "C15") (pin "2") (pinfunction "2_2") (pintype "passive"))
      (node (ref "C16") (pin "2") (pinfunction "2_2") (pintype "passive"))
      (node (ref "C17") (pin "2") (pinfunction "2_2") (pintype "passive"))
      (node (ref "C18") (pin "2") (pinfunction "2_2") (pintype "passive"))
      (node (ref "C19") (pin "2") (pinfunction "2_2") (pintype "passive"))
      (node (ref "C2") (pin "2") (pinfunction "2_2") (pintype "passive"))
      (node (ref "C20") (pin "2") (pinfunction "2_2") (pintype "passive"))
      (node (ref "C21") (pin "2") (pinfunction "2_2") (pintype "passive"))
      (node (ref "C22") (pin "2") (pinfunction "2_2") (pintype "passive"))
      (node (ref "C23") (pin "2") (pinfunction "2_2") (pintype "passive"))
      (node (ref "C24") (pin "2") (pinfunction "2_2") (pintype "passive"))
      (node (ref "C25") (pin "2") (pinfunction "2_2") (pintype "passive"))
      (node (ref "C26") (pin "2") (pinfunction "2_2") (pintype "passive"))
      (node (ref "C27") (pin "2") (pinfunction "2_2") (pintype "passive"))
      (node (ref "C28") (pin "2") (pinfunction "2_2") (pintype "passive"))
      (node (ref "C29") (pin "2") (pinfunction "2_2") (pintype "passive"))
      (node (ref "C3") (pin "2") (pinfunction "2_2") (pintype "passive"))
      (node (ref "C30") (pin "2") (pinfunction "2_2") (pintype "passive"))
      (node (ref "C31") (pin "2") (pinfunction "2_2") (pintype "passive"))
      (node (ref "C32") (pin "2") (pinfunction "2_2") (pintype "passive"))
      (node (ref "C33") (pin "2") (pinfunction "2_2") (pintype "passive"))
      (node (ref "C34") (pin "2") (pinfunction "2_2") (pintype "passive"))
      (node (ref "C35") (pin "2") (pinfunction "2_2") (pintype "passive"))
      (node (ref "C36") (pin "2") (pinfunction "2_2") (pintype "passive"))
      (node (ref "C37") (pin "2") (pinfunction "2_2") (pintype "passive"))
      (node (ref "C38") (pin "2") (pinfunction "2_2") (pintype "passive"))
      (node (ref "C39") (pin "2") (pinfunction "2_2") (pintype "passive"))
      (node (ref "C4") (pin "2") (pinfunction "2_2") (pintype "passive"))
      (node (ref "C40") (pin "2") (pinfunction "2_2") (pintype "passive"))
      (node (ref "C41") (pin "2") (pinfunction "2_2") (pintype "passive"))
      (node (ref "C42") (pin "-") (pinfunction "-_-") (pintype "passive"))
      (node (ref "C43") (pin "-") (pinfunction "-_-") (pintype "passive"))
      (node (ref "C44") (pin "-") (pinfunction "-_-") (pintype "passive"))
      (node (ref "C45") (pin "-") (pinfunction "-_-") (pintype "passive"))
      (node (ref "C5") (pin "2") (pinfunction "2_2") (pintype "passive"))
      (node (ref "C6") (pin "2") (pinfunction "2_2") (pintype "passive"))
      (node (ref "C7") (pin "2") (pinfunction "2_2") (pintype "passive"))
      (node (ref "C8") (pin "2") (pinfunction "2_2") (pintype "passive"))
      (node (ref "C9") (pin "2") (pinfunction "2_2") (pintype "passive"))
      (node (ref "DRIVE") (pin "A") (pinfunction "1_A") (pintype "bidirectional"))
      (node (ref "DRIVE") (pin "AA") (pinfunction "23_AA") (pintype "bidirectional"))
      (node (ref "DRIVE") (pin "B") (pinfunction "2_B") (pintype "bidirectional"))
      (node (ref "DRIVE") (pin "C") (pinfunction "3_C") (pintype "bidirectional"))
      (node (ref "DRIVE") (pin "CC") (pinfunction "25_CC") (pintype "bidirectional"))
      (node (ref "DRIVE") (pin "DD") (pinfunction "26_DD") (pintype "bidirectional"))
      (node (ref "DRIVE") (pin "E") (pinfunction "5_E") (pintype "bidirectional"))
      (node (ref "DRIVE") (pin "EE") (pinfunction "27_EE") (pintype "bidirectional"))
      (node (ref "DRIVE") (pin "F") (pinfunction "6_F") (pintype "bidirectional"))
      (node (ref "DRIVE") (pin "H") (pinfunction "7_H") (pintype "bidirectional"))
      (node (ref "DRIVE") (pin "HH") (pinfunction "29_HH") (pintype "bidirectional"))
      (node (ref "DRIVE") (pin "JJ") (pinfunction "30_JJ") (pintype "bidirectional"))
      (node (ref "DRIVE") (pin "K") (pinfunction "9_K") (pintype "bidirectional"))
      (node (ref "DRIVE") (pin "KK") (pinfunction "31_KK") (pintype "bidirectional"))
      (node (ref "DRIVE") (pin "L") (pinfunction "10_L") (pintype "bidirectional"))
      (node (ref "DRIVE") (pin "M") (pinfunction "11_M") (pintype "bidirectional"))
      (node (ref "DRIVE") (pin "MM") (pinfunction "33_MM") (pintype "bidirectional"))
      (node (ref "DRIVE") (pin "NN") (pinfunction "34_NN") (pintype "bidirectional"))
      (node (ref "DRIVE") (pin "P") (pinfunction "13_P") (pintype "bidirectional"))
      (node (ref "DRIVE") (pin "PP") (pinfunction "35_PP") (pintype "bidirectional"))
      (node (ref "DRIVE") (pin "R") (pinfunction "14_R") (pintype "bidirectional"))
      (node (ref "DRIVE") (pin "S") (pinfunction "15_S") (pintype "bidirectional"))
      (node (ref "DRIVE") (pin "SS") (pinfunction "37_SS") (pintype "bidirectional"))
      (node (ref "DRIVE") (pin "TT") (pinfunction "38_TT") (pintype "bidirectional"))
      (node (ref "DRIVE") (pin "U") (pinfunction "17_U") (pintype "bidirectional"))
      (node (ref "DRIVE") (pin "UU") (pinfunction "39_UU") (pintype "bidirectional"))
      (node (ref "DRIVE") (pin "V") (pinfunction "18_V") (pintype "bidirectional"))
      (node (ref "DRIVE") (pin "VV") (pinfunction "40_VV") (pintype "bidirectional"))
      (node (ref "DRIVE") (pin "W") (pinfunction "19_W") (pintype "bidirectional"))
      (node (ref "DRIVE") (pin "Y") (pinfunction "21_Y") (pintype "bidirectional"))
      (node (ref "DRIVE") (pin "Z") (pinfunction "22_Z") (pintype "bidirectional"))
      (node (ref "E11") (pin "10") (pinfunction "I1_10") (pintype "input"))
      (node (ref "E11") (pin "5") (pinfunction "I1_5") (pintype "input"))
      (node (ref "E11") (pin "7") (pinfunction "I1_7") (pintype "input"))
      (node (ref "E39") (pin "7") (pinfunction "I1_7") (pintype "input"))
      (node (ref "E4") (pin "6") (pinfunction "D_6") (pintype "input"))
      (node (ref "R10") (pin "1") (pinfunction "1_1") (pintype "passive"))
      (node (ref "R11") (pin "1") (pinfunction "1_1") (pintype "passive"))
      (node (ref "R12") (pin "1") (pinfunction "1_1") (pintype "passive"))
      (node (ref "R13") (pin "1") (pinfunction "1_1") (pintype "passive"))
      (node (ref "R14") (pin "1") (pinfunction "1_1") (pintype "passive"))
      (node (ref "R15") (pin "1") (pinfunction "1_1") (pintype "passive"))
      (node (ref "R16") (pin "1") (pinfunction "1_1") (pintype "passive"))
      (node (ref "R17") (pin "1") (pinfunction "1_1") (pintype "passive"))
      (node (ref "U$2") (pin "AC2") (pinfunction "1_AC2") (pintype "bidirectional"))
      (node (ref "U$2") (pin "AT1") (pinfunction "1_AT1") (pintype "bidirectional"))
      (node (ref "U$2") (pin "AT2") (pinfunction "1_AT2") (pintype "bidirectional"))
      (node (ref "U$2") (pin "BC2") (pinfunction "1_BC2") (pintype "bidirectional"))
      (node (ref "U$2") (pin "BT1") (pinfunction "1_BT1") (pintype "bidirectional"))
      (node (ref "U$2") (pin "CC2") (pinfunction "1_CC2") (pintype "bidirectional"))
      (node (ref "U$2") (pin "CT1") (pinfunction "1_CT1") (pintype "bidirectional"))
      (node (ref "U$2") (pin "DC2") (pinfunction "1_DC2") (pintype "bidirectional"))
      (node (ref "U$2") (pin "DT1") (pinfunction "1_DT1") (pintype "bidirectional"))
    )
    (net (code "23") (name "INIT") (class "Default")
      (node (ref "E19") (pin "6") (pinfunction "I1_6") (pintype "input"))
      (node (ref "E23") (pin "3") (pinfunction "I1_3") (pintype "input"))
      (node (ref "E23") (pin "6") (pinfunction "I1_6") (pintype "input"))
      (node (ref "E24") (pin "3") (pinfunction "O_3") (pintype "output"))
      (node (ref "E32") (pin "3") (pinfunction "I_3") (pintype "input"))
      (node (ref "E6") (pin "12") (pinfunction "I1_12") (pintype "input"))
      (node (ref "E8") (pin "5") (pinfunction "I_5") (pintype "input"))
      (node (ref "X37") (pin "12") (pinfunction "I0_12") (pintype "input"))
      (node (ref "X37") (pin "13") (pinfunction "I1_13") (pintype "input"))
    )
    (net (code "24") (name "INITIALIZE") (class "Default")
      (node (ref "E11") (pin "6") (pinfunction "I0_6") (pintype "input"))
      (node (ref "U$2") (pin "CR1") (pinfunction "1_CR1") (pintype "bidirectional"))
    )
    (net (code "25") (name "LCD_IOT") (class "Default")
      (node (ref "E12") (pin "10") (pinfunction "I1_10") (pintype "input"))
      (node (ref "E28") (pin "4") (pinfunction "I2_4") (pintype "input"))
      (node (ref "E38") (pin "4") (pinfunction "O_4") (pintype "output"))
    )
    (net (code "26") (name "MAINT") (class "Default")
      (node (ref "E2") (pin "9") (pinfunction "Q_9") (pintype "output"))
      (node (ref "E20") (pin "9") (pinfunction "I0_9") (pintype "input"))
    )
    (net (code "27") (name "MSB8") (class "Default")
      (node (ref "E21") (pin "11") (pinfunction "QD_11") (pintype "output"))
      (node (ref "E3") (pin "5") (pinfunction "I2_5") (pintype "input"))
      (node (ref "E9") (pin "4") (pinfunction "SER_4") (pintype "input"))
      (node (ref "X17") (pin "1") (pinfunction "I0_1") (pintype "input"))
    )
    (net (code "28") (name "MSB12") (class "Default")
      (node (ref "E3") (pin "2") (pinfunction "I1_2") (pintype "input"))
      (node (ref "E9") (pin "11") (pinfunction "QD_11") (pintype "output"))
      (node (ref "X5") (pin "1") (pinfunction "I0_1") (pintype "input"))
    )
    (net (code "29") (name "Net-(E2A-CLK)") (class "Default")
      (node (ref "E2") (pin "11") (pinfunction "CLK_11") (pintype "input"))
      (node (ref "E2") (pin "3") (pinfunction "CLK_3") (pintype "input"))
      (node (ref "E6") (pin "1") (pinfunction "O_1") (pintype "output"))
    )
    (net (code "30") (name "Net-(E3A-I2)") (class "Default")
      (node (ref "E3") (pin "13") (pinfunction "I2_13") (pintype "input"))
      (node (ref "E3") (pin "3") (pinfunction "I0_3") (pintype "input"))
      (node (ref "E8") (pin "2") (pinfunction "O_2") (pintype "output"))
    )
    (net (code "31") (name "Net-(E3A-O)") (class "Default")
      (node (ref "E3") (pin "11") (pinfunction "I2_11") (pintype "input"))
      (node (ref "E3") (pin "12") (pinfunction "O_12") (pintype "output"))
    )
    (net (code "32") (name "Net-(E3B-O)") (class "Default")
      (node (ref "E3") (pin "6") (pinfunction "O_6") (pintype "output"))
      (node (ref "E3") (pin "9") (pinfunction "I0_9") (pintype "input"))
    )
    (net (code "33") (name "Net-(E4A-CLK)") (class "Default")
      (node (ref "E4") (pin "2") (pinfunction "CLK_2") (pintype "input"))
      (node (ref "E8") (pin "13") (pinfunction "I_13") (pintype "input"))
      (node (ref "E8") (pin "4") (pinfunction "O_4") (pintype "output"))
    )
    (net (code "34") (name "Net-(E9A-QA)") (class "Default")
      (node (ref "E9") (pin "5") (pinfunction "QA_5") (pintype "output"))
      (node (ref "X5") (pin "12") (pinfunction "I0_12") (pintype "input"))
    )
    (net (code "35") (name "Net-(E9A-QB)") (class "Default")
      (node (ref "E9") (pin "7") (pinfunction "QB_7") (pintype "output"))
      (node (ref "X5") (pin "9") (pinfunction "I0_9") (pintype "input"))
    )
    (net (code "36") (name "Net-(E9A-QC)") (class "Default")
      (node (ref "E9") (pin "9") (pinfunction "QC_9") (pintype "output"))
      (node (ref "X5") (pin "4") (pinfunction "I0_4") (pintype "input"))
    )
    (net (code "37") (name "Net-(E10A-I1)") (class "Default")
      (node (ref "E10") (pin "2") (pinfunction "I1_2") (pintype "input"))
      (node (ref "E10") (pin "6") (pinfunction "O_6") (pintype "output"))
      (node (ref "X14") (pin "12") (pinfunction "I0_12") (pintype "input"))
    )
    (net (code "38") (name "Net-(E10A-O)") (class "Default")
      (node (ref "E10") (pin "12") (pinfunction "O_12") (pintype "output"))
      (node (ref "E12") (pin "5") (pinfunction "I1_5") (pintype "input"))
    )
    (net (code "39") (name "Net-(E10C-O)") (class "Default")
      (node (ref "E10") (pin "8") (pinfunction "O_8") (pintype "output"))
      (node (ref "E18X") (pin "10") (pinfunction "I1_10") (pintype "input"))
      (node (ref "E18X") (pin "9") (pinfunction "I0_9") (pintype "input"))
    )
    (net (code "40") (name "Net-(E11A-O)") (class "Default")
      (node (ref "E11") (pin "3") (pinfunction "O_3") (pintype "output"))
      (node (ref "E7") (pin "4") (pinfunction "PRE_4") (pintype "input"))
      (node (ref "E8") (pin "9") (pinfunction "I_9") (pintype "input"))
    )
    (net (code "41") (name "Net-(E11B-O)") (class "Default")
      (node (ref "E11") (pin "2") (pinfunction "O_2") (pintype "output"))
      (node (ref "E24") (pin "1") (pinfunction "I0_1") (pintype "input"))
    )
    (net (code "42") (name "Net-(E12A-I0)") (class "Default")
      (node (ref "E12") (pin "1") (pinfunction "I0_1") (pintype "input"))
      (node (ref "E12") (pin "11") (pinfunction "O_11") (pintype "output"))
    )
    (net (code "43") (name "Net-(E12A-I1)") (class "Default")
      (node (ref "E12") (pin "2") (pinfunction "I1_2") (pintype "input"))
      (node (ref "E12") (pin "8") (pinfunction "O_8") (pintype "output"))
    )
    (net (code "44") (name "Net-(E12A-O)") (class "Default")
      (node (ref "E12") (pin "3") (pinfunction "O_3") (pintype "output"))
      (node (ref "E4") (pin "5") (pinfunction "C_5") (pintype "input"))
    )
    (net (code "45") (name "Net-(E12B-O)") (class "Default")
      (node (ref "E12") (pin "6") (pinfunction "O_6") (pintype "output"))
      (node (ref "X14") (pin "1") (pinfunction "I0_1") (pintype "input"))
      (node (ref "X14") (pin "2") (pinfunction "I1_2") (pintype "input"))
    )
    (net (code "46") (name "Net-(E15A-CLK)") (class "Default")
      (node (ref "E15") (pin "3") (pinfunction "CLK_3") (pintype "input"))
      (node (ref "E6") (pin "4") (pinfunction "O_4") (pintype "output"))
    )
    (net (code "47") (name "Net-(E15A-Q)") (class "Default")
      (node (ref "E15") (pin "5") (pinfunction "Q_5") (pintype "output"))
      (node (ref "E18X") (pin "5") (pinfunction "I1_5") (pintype "input"))
    )
    (net (code "48") (name "Net-(E15B-CLK)") (class "Default")
      (node (ref "E15") (pin "11") (pinfunction "CLK_11") (pintype "input"))
      (node (ref "E24") (pin "6") (pinfunction "O_6") (pintype "output"))
    )
    (net (code "49") (name "Net-(E15B-CLR)") (class "Default")
      (node (ref "E15") (pin "13") (pinfunction "CLR_13") (pintype "input"))
      (node (ref "E16") (pin "8") (pinfunction "O_8") (pintype "output"))
    )
    (net (code "50") (name "Net-(E16A-I1)") (class "Default")
      (node (ref "E16") (pin "2") (pinfunction "I1_2") (pintype "input"))
      (node (ref "E19") (pin "13") (pinfunction "O_13") (pintype "output"))
      (node (ref "X17") (pin "10") (pinfunction "I1_10") (pintype "input"))
      (node (ref "X17") (pin "13") (pinfunction "I1_13") (pintype "input"))
      (node (ref "X17") (pin "2") (pinfunction "I1_2") (pintype "input"))
      (node (ref "X17") (pin "5") (pinfunction "I1_5") (pintype "input"))
      (node (ref "X29") (pin "10") (pinfunction "I1_10") (pintype "input"))
      (node (ref "X29") (pin "13") (pinfunction "I1_13") (pintype "input"))
      (node (ref "X29") (pin "2") (pinfunction "I1_2") (pintype "input"))
      (node (ref "X29") (pin "5") (pinfunction "I1_5") (pintype "input"))
    )
    (net (code "51") (name "Net-(E16A-O)") (class "Default")
      (node (ref "E16") (pin "3") (pinfunction "O_3") (pintype "output"))
      (node (ref "X5") (pin "10") (pinfunction "I1_10") (pintype "input"))
      (node (ref "X5") (pin "13") (pinfunction "I1_13") (pintype "input"))
      (node (ref "X5") (pin "2") (pinfunction "I1_2") (pintype "input"))
      (node (ref "X5") (pin "5") (pinfunction "I1_5") (pintype "input"))
    )
    (net (code "52") (name "Net-(E16B-O)") (class "Default")
      (node (ref "E16") (pin "6") (pinfunction "O_6") (pintype "output"))
      (node (ref "E20") (pin "2") (pinfunction "I1_2") (pintype "input"))
    )
    (net (code "53") (name "Net-(E16C-I0)") (class "Default")
      (node (ref "E16") (pin "9") (pinfunction "I0_9") (pintype "input"))
      (node (ref "E24") (pin "9") (pinfunction "I0_9") (pintype "input"))
      (node (ref "E39") (pin "13") (pinfunction "O_13") (pintype "output"))
    )
    (net (code "54") (name "Net-(E16D-I1)") (class "Default")
      (node (ref "E16") (pin "13") (pinfunction "I1_13") (pintype "input"))
      (node (ref "E24") (pin "8") (pinfunction "O_8") (pintype "output"))
    )
    (net (code "55") (name "Net-(E18XA-I0)") (class "Default")
      (node (ref "E18X") (pin "1") (pinfunction "I0_1") (pintype "input"))
      (node (ref "E18X") (pin "2") (pinfunction "I1_2") (pintype "input"))
      (node (ref "E32") (pin "5") (pinfunction "I_5") (pintype "input"))
      (node (ref "E35") (pin "3") (pinfunction "O_3") (pintype "output"))
      (node (ref "E38") (pin "1") (pinfunction "I_1") (pintype "input"))
    )
    (net (code "56") (name "Net-(E18XB-I0)") (class "Default")
      (node (ref "E18X") (pin "4") (pinfunction "I0_4") (pintype "input"))
      (node (ref "E22") (pin "9") (pinfunction "Q_9") (pintype "output"))
      (node (ref "E34") (pin "13") (pinfunction "I1_13") (pintype "input"))
    )
    (net (code "57") (name "Net-(E19A-I0)") (class "Default")
      (node (ref "E19") (pin "2") (pinfunction "I0_2") (pintype "input"))
      (node (ref "E20") (pin "12") (pinfunction "O_12") (pintype "output"))
    )
    (net (code "58") (name "Net-(E19B-I0)") (class "Default")
      (node (ref "E19") (pin "10") (pinfunction "O_10") (pintype "output"))
      (node (ref "E19") (pin "5") (pinfunction "I0_5") (pintype "input"))
    )
    (net (code "59") (name "Net-(E19B-O)") (class "Default")
      (node (ref "E19") (pin "4") (pinfunction "O_4") (pintype "output"))
      (node (ref "E22") (pin "1") (pinfunction "CLR_1") (pintype "input"))
    )
    (net (code "60") (name "Net-(E19D-I0)") (class "Default")
      (node (ref "E19") (pin "11") (pinfunction "I0_11") (pintype "input"))
      (node (ref "E20") (pin "8") (pinfunction "O_8") (pintype "output"))
    )
    (net (code "61") (name "Net-(E21A-QA)") (class "Default")
      (node (ref "E21") (pin "5") (pinfunction "QA_5") (pintype "output"))
      (node (ref "X17") (pin "12") (pinfunction "I0_12") (pintype "input"))
    )
    (net (code "62") (name "Net-(E21A-QB)") (class "Default")
      (node (ref "E21") (pin "7") (pinfunction "QB_7") (pintype "output"))
      (node (ref "X17") (pin "9") (pinfunction "I0_9") (pintype "input"))
    )
    (net (code "63") (name "Net-(E21A-QC)") (class "Default")
      (node (ref "E21") (pin "9") (pinfunction "QC_9") (pintype "output"))
      (node (ref "X17") (pin "4") (pinfunction "I0_4") (pintype "input"))
    )
    (net (code "64") (name "Net-(E21A-SER)") (class "Default")
      (node (ref "E21") (pin "4") (pinfunction "SER_4") (pintype "input"))
      (node (ref "E33") (pin "11") (pinfunction "QD_11") (pintype "output"))
      (node (ref "X29") (pin "1") (pinfunction "I0_1") (pintype "input"))
    )
    (net (code "65") (name "Net-(E22A-Q)") (class "Default")
      (node (ref "E22") (pin "12") (pinfunction "D_12") (pintype "input"))
      (node (ref "E22") (pin "5") (pinfunction "Q_5") (pintype "output"))
    )
    (net (code "66") (name "Net-(E23A-I0)") (class "Default")
      (node (ref "E23") (pin "13") (pinfunction "O_13") (pintype "output"))
      (node (ref "E23") (pin "2") (pinfunction "I0_2") (pintype "input"))
    )
    (net (code "67") (name "Net-(E23A-O)") (class "Default")
      (node (ref "E23") (pin "1") (pinfunction "O_1") (pintype "output"))
      (node (ref "E30") (pin "1") (pinfunction "CLR_1") (pintype "input"))
    )
    (net (code "68") (name "Net-(E23B-I0)") (class "Default")
      (node (ref "E23") (pin "10") (pinfunction "O_10") (pintype "output"))
      (node (ref "E23") (pin "5") (pinfunction "I0_5") (pintype "input"))
    )
    (net (code "69") (name "Net-(E23B-O)") (class "Default")
      (node (ref "E23") (pin "4") (pinfunction "O_4") (pintype "output"))
      (node (ref "E26") (pin "1") (pinfunction "CLR_1") (pintype "input"))
    )
    (net (code "70") (name "Net-(E24A-I1)") (class "Default")
      (node (ref "E24") (pin "2") (pinfunction "I1_2") (pintype "input"))
      (node (ref "E7") (pin "5") (pinfunction "Q_5") (pintype "output"))
    )
    (net (code "71") (name "Net-(E24B-I0)") (class "Default")
      (node (ref "E24") (pin "4") (pinfunction "I0_4") (pintype "input"))
      (node (ref "E28") (pin "8") (pinfunction "O_8") (pintype "output"))
    )
    (net (code "72") (name "Net-(E24B-I1)") (class "Default")
      (node (ref "E24") (pin "5") (pinfunction "I1_5") (pintype "input"))
      (node (ref "E28") (pin "6") (pinfunction "O_6") (pintype "output"))
    )
    (net (code "73") (name "Net-(E24D-O)") (class "Default")
      (node (ref "E24") (pin "11") (pinfunction "O_11") (pintype "output"))
      (node (ref "E3") (pin "10") (pinfunction "I1_10") (pintype "input"))
    )
    (net (code "74") (name "Net-(E26A-Q)") (class "Default")
      (node (ref "E26") (pin "12") (pinfunction "D_12") (pintype "input"))
      (node (ref "E26") (pin "5") (pinfunction "Q_5") (pintype "output"))
    )
    (net (code "75") (name "Net-(E26B-Q)") (class "Default")
      (node (ref "E26") (pin "9") (pinfunction "Q_9") (pintype "output"))
      (node (ref "E34") (pin "1") (pinfunction "I0_1") (pintype "input"))
    )
    (net (code "76") (name "Net-(E27A-CLR)") (class "Default")
      (node (ref "E27") (pin "3") (pinfunction "CLR_3") (pintype "input"))
      (node (ref "E6") (pin "13") (pinfunction "O_13") (pintype "output"))
    )
    (net (code "77") (name "Net-(E27A-J)") (class "Default")
      (node (ref "E27") (pin "16") (pinfunction "K_16") (pintype "input"))
      (node (ref "E27") (pin "4") (pinfunction "J_4") (pintype "input"))
      (node (ref "E3") (pin "8") (pinfunction "O_8") (pintype "output"))
      (node (ref "X14") (pin "5") (pinfunction "I1_5") (pintype "input"))
    )
    (net (code "78") (name "Net-(E30A-Q)") (class "Default")
      (node (ref "E30") (pin "12") (pinfunction "D_12") (pintype "input"))
      (node (ref "E30") (pin "5") (pinfunction "Q_5") (pintype "output"))
    )
    (net (code "79") (name "Net-(E30B-Q)") (class "Default")
      (node (ref "E30") (pin "9") (pinfunction "Q_9") (pintype "output"))
      (node (ref "E34") (pin "10") (pinfunction "I1_10") (pintype "input"))
    )
    (net (code "80") (name "Net-(E33A-QA)") (class "Default")
      (node (ref "E33") (pin "5") (pinfunction "QA_5") (pintype "output"))
      (node (ref "X29") (pin "12") (pinfunction "I0_12") (pintype "input"))
    )
    (net (code "81") (name "Net-(E33A-QB)") (class "Default")
      (node (ref "E33") (pin "7") (pinfunction "QB_7") (pintype "output"))
      (node (ref "X29") (pin "9") (pinfunction "I0_9") (pintype "input"))
    )
    (net (code "82") (name "Net-(E33A-QC)") (class "Default")
      (node (ref "E33") (pin "9") (pinfunction "QC_9") (pintype "output"))
      (node (ref "X29") (pin "4") (pinfunction "I0_4") (pintype "input"))
    )
    (net (code "83") (name "Net-(E34A-I1)") (class "Default")
      (node (ref "E34") (pin "2") (pinfunction "I1_2") (pintype "input"))
      (node (ref "E38") (pin "8") (pinfunction "O_8") (pintype "output"))
    )
    (net (code "84") (name "Net-(E34C-I0)") (class "Default")
      (node (ref "E34") (pin "9") (pinfunction "I0_9") (pintype "input"))
      (node (ref "E38") (pin "12") (pinfunction "O_12") (pintype "output"))
    )
    (net (code "85") (name "Net-(E34D-I0)") (class "Default")
      (node (ref "E34") (pin "12") (pinfunction "I0_12") (pintype "input"))
      (node (ref "E38") (pin "10") (pinfunction "O_10") (pintype "output"))
    )
    (net (code "86") (name "Net-(E35A-I3)") (class "Default")
      (node (ref "E35") (pin "9") (pinfunction "I3_9") (pintype "input"))
      (node (ref "E39") (pin "2") (pinfunction "O_2") (pintype "output"))
      (node (ref "E40") (pin "7") (pinfunction "FORCE0_7") (pintype "input"))
    )
    (net (code "87") (name "Net-(E35A-I4)") (class "Default")
      (node (ref "E31") (pin "11") (pinfunction "11_11") (pintype "passive"))
      (node (ref "E31") (pin "14") (pinfunction "14_14") (pintype "passive"))
      (node (ref "E35") (pin "10") (pinfunction "I4_10") (pintype "input"))
    )
    (net (code "88") (name "Net-(E35A-I5)") (class "Default")
      (node (ref "E31") (pin "12") (pinfunction "12_12") (pintype "passive"))
      (node (ref "E31") (pin "15") (pinfunction "15_15") (pintype "passive"))
      (node (ref "E35") (pin "11") (pinfunction "I5_11") (pintype "input"))
    )
    (net (code "89") (name "Net-(E35A-I6)") (class "Default")
      (node (ref "E31") (pin "13") (pinfunction "13_13") (pintype "passive"))
      (node (ref "E31") (pin "16") (pinfunction "16_16") (pintype "passive"))
      (node (ref "E35") (pin "12") (pinfunction "I6_12") (pintype "input"))
    )
    (net (code "90") (name "Net-(E38A-O)") (class "Default")
      (node (ref "E38") (pin "2") (pinfunction "O_2") (pintype "output"))
      (node (ref "E40") (pin "9") (pinfunction "FORCE0_9") (pintype "input"))
      (node (ref "E41") (pin "12") (pinfunction "D_12") (pintype "input"))
    )
    (net (code "91") (name "Net-(E40A-A1)") (class "Default")
      (node (ref "E31") (pin "1") (pinfunction "1_1") (pintype "passive"))
      (node (ref "E40") (pin "2") (pinfunction "A1_2") (pintype "output"))
    )
    (net (code "92") (name "Net-(E40A-A2)") (class "Default")
      (node (ref "E31") (pin "2") (pinfunction "2_2") (pintype "passive"))
      (node (ref "E40") (pin "4") (pinfunction "A2_4") (pintype "output"))
    )
    (net (code "93") (name "Net-(E40A-A3)") (class "Default")
      (node (ref "E31") (pin "3") (pinfunction "3_3") (pintype "passive"))
      (node (ref "E40") (pin "6") (pinfunction "A3_6") (pintype "output"))
    )
    (net (code "94") (name "Net-(E40B-A1)") (class "Default")
      (node (ref "E40") (pin "10") (pinfunction "A1_10") (pintype "output"))
      (node (ref "E41") (pin "15") (pinfunction "A_15") (pintype "input"))
    )
    (net (code "95") (name "Net-(E40B-A2)") (class "Default")
      (node (ref "E40") (pin "12") (pinfunction "A2_12") (pintype "output"))
      (node (ref "E41") (pin "14") (pinfunction "B_14") (pintype "input"))
    )
    (net (code "96") (name "Net-(E40B-A3)") (class "Default")
      (node (ref "E40") (pin "14") (pinfunction "A3_14") (pintype "output"))
      (node (ref "E41") (pin "13") (pinfunction "C_13") (pintype "input"))
    )
    (net (code "97") (name "Net-(PAD10-P)") (class "Default")
      (node (ref "E13") (pin "1") (pinfunction "1_1") (pintype "passive"))
      (node (ref "PAD10") (pin "1") (pinfunction "P_1") (pintype "passive"))
    )
    (net (code "98") (name "Net-(PAD11-P)") (class "Default")
      (node (ref "E13") (pin "2") (pinfunction "2_2") (pintype "passive"))
      (node (ref "PAD11") (pin "1") (pinfunction "P_1") (pintype "passive"))
    )
    (net (code "99") (name "Net-(PAD12-P)") (class "Default")
      (node (ref "E13") (pin "3") (pinfunction "3_3") (pintype "passive"))
      (node (ref "PAD12") (pin "1") (pinfunction "P_1") (pintype "passive"))
    )
    (net (code "100") (name "Net-(PAD13-P)") (class "Default")
      (node (ref "E13") (pin "4") (pinfunction "4_4") (pintype "passive"))
      (node (ref "PAD13") (pin "1") (pinfunction "P_1") (pintype "passive"))
    )
    (net (code "101") (name "Net-(PAD14-P)") (class "Default")
      (node (ref "E13") (pin "5") (pinfunction "5_5") (pintype "passive"))
      (node (ref "PAD14") (pin "1") (pinfunction "P_1") (pintype "passive"))
    )
    (net (code "102") (name "Net-(PAD15-P)") (class "Default")
      (node (ref "E13") (pin "6") (pinfunction "6_6") (pintype "passive"))
      (node (ref "PAD15") (pin "1") (pinfunction "P_1") (pintype "passive"))
    )
    (net (code "103") (name "Net-(PAD16-P)") (class "Default")
      (node (ref "E13") (pin "7") (pinfunction "7_7") (pintype "passive"))
      (node (ref "PAD16") (pin "1") (pinfunction "P_1") (pintype "passive"))
    )
    (net (code "104") (name "Net-(PAD17-P)") (class "Default")
      (node (ref "E13") (pin "8") (pinfunction "8_8") (pintype "passive"))
      (node (ref "PAD17") (pin "1") (pinfunction "P_1") (pintype "passive"))
    )
    (net (code "105") (name "Net-(PAD20-P)") (class "Default")
      (node (ref "E13") (pin "16") (pinfunction "16_16") (pintype "passive"))
      (node (ref "PAD20") (pin "1") (pinfunction "P_1") (pintype "passive"))
    )
    (net (code "106") (name "Net-(PAD21-P)") (class "Default")
      (node (ref "E13") (pin "15") (pinfunction "15_15") (pintype "passive"))
      (node (ref "PAD21") (pin "1") (pinfunction "P_1") (pintype "passive"))
    )
    (net (code "107") (name "Net-(PAD22-P)") (class "Default")
      (node (ref "E13") (pin "14") (pinfunction "14_14") (pintype "passive"))
      (node (ref "PAD22") (pin "1") (pinfunction "P_1") (pintype "passive"))
    )
    (net (code "108") (name "Net-(PAD23-P)") (class "Default")
      (node (ref "E13") (pin "13") (pinfunction "13_13") (pintype "passive"))
      (node (ref "PAD23") (pin "1") (pinfunction "P_1") (pintype "passive"))
    )
    (net (code "109") (name "Net-(PAD24-P)") (class "Default")
      (node (ref "E13") (pin "12") (pinfunction "12_12") (pintype "passive"))
      (node (ref "PAD24") (pin "1") (pinfunction "P_1") (pintype "passive"))
    )
    (net (code "110") (name "Net-(PAD25-P)") (class "Default")
      (node (ref "E13") (pin "11") (pinfunction "11_11") (pintype "passive"))
      (node (ref "PAD25") (pin "1") (pinfunction "P_1") (pintype "passive"))
    )
    (net (code "111") (name "Net-(PAD26-P)") (class "Default")
      (node (ref "E13") (pin "10") (pinfunction "10_10") (pintype "passive"))
      (node (ref "PAD26") (pin "1") (pinfunction "P_1") (pintype "passive"))
    )
    (net (code "112") (name "Net-(PAD27-P)") (class "Default")
      (node (ref "E13") (pin "9") (pinfunction "9_9") (pintype "passive"))
      (node (ref "PAD27") (pin "1") (pinfunction "P_1") (pintype "passive"))
    )
    (net (code "113") (name "PARITY") (class "Default")
      (node (ref "E24") (pin "13") (pinfunction "I1_13") (pintype "input"))
      (node (ref "E4") (pin "15") (pinfunction "RCO_15") (pintype "output"))
      (node (ref "E8") (pin "1") (pinfunction "I_1") (pintype "input"))
      (node (ref "U$2") (pin "AB1") (pinfunction "1_AB1") (pintype "bidirectional"))
    )
    (net (code "114") (name "RD") (class "Default")
      (node (ref "E20") (pin "10") (pinfunction "I1_10") (pintype "input"))
      (node (ref "E32") (pin "1") (pinfunction "I_1") (pintype "input"))
      (node (ref "E36") (pin "14") (pinfunction "A3_14") (pintype "output"))
    )
    (net (code "115") (name "RUN") (class "Default")
      (node (ref "E15") (pin "9") (pinfunction "Q_9") (pintype "output"))
      (node (ref "E18X") (pin "12") (pinfunction "I0_12") (pintype "input"))
      (node (ref "E18X") (pin "13") (pinfunction "I1_13") (pintype "input"))
      (node (ref "E6") (pin "11") (pinfunction "I0_11") (pintype "input"))
    )
    (net (code "116") (name "RX_DATA") (class "Default")
      (node (ref "E33") (pin "4") (pinfunction "SER_4") (pintype "input"))
      (node (ref "E36") (pin "10") (pinfunction "A1_10") (pintype "output"))
    )
    (net (code "117") (name "SHIFT") (class "Default")
      (node (ref "E19") (pin "3") (pinfunction "I1_3") (pintype "input"))
      (node (ref "E36") (pin "12") (pinfunction "A2_12") (pintype "output"))
    )
    (net (code "118") (name "TP3") (class "Default")
      (node (ref "E11") (pin "9") (pinfunction "I0_9") (pintype "input"))
      (node (ref "U$2") (pin "CH2") (pinfunction "1_CH2") (pintype "bidirectional"))
    )
    (net (code "119") (name "TP4") (class "Default")
      (node (ref "E11") (pin "4") (pinfunction "I0_4") (pintype "input"))
      (node (ref "U$2") (pin "CJ2") (pinfunction "1_CJ2") (pintype "bidirectional"))
    )
    (net (code "120") (name "VCC") (class "Default")
      (node (ref "C1") (pin "1") (pinfunction "1_1") (pintype "passive"))
      (node (ref "C10") (pin "1") (pinfunction "1_1") (pintype "passive"))
      (node (ref "C11") (pin "1") (pinfunction "1_1") (pintype "passive"))
      (node (ref "C12") (pin "1") (pinfunction "1_1") (pintype "passive"))
      (node (ref "C13") (pin "1") (pinfunction "1_1") (pintype "passive"))
      (node (ref "C14") (pin "1") (pinfunction "1_1") (pintype "passive"))
      (node (ref "C15") (pin "1") (pinfunction "1_1") (pintype "passive"))
      (node (ref "C16") (pin "1") (pinfunction "1_1") (pintype "passive"))
      (node (ref "C17") (pin "1") (pinfunction "1_1") (pintype "passive"))
      (node (ref "C18") (pin "1") (pinfunction "1_1") (pintype "passive"))
      (node (ref "C19") (pin "1") (pinfunction "1_1") (pintype "passive"))
      (node (ref "C2") (pin "1") (pinfunction "1_1") (pintype "passive"))
      (node (ref "C20") (pin "1") (pinfunction "1_1") (pintype "passive"))
      (node (ref "C21") (pin "1") (pinfunction "1_1") (pintype "passive"))
      (node (ref "C22") (pin "1") (pinfunction "1_1") (pintype "passive"))
      (node (ref "C23") (pin "1") (pinfunction "1_1") (pintype "passive"))
      (node (ref "C24") (pin "1") (pinfunction "1_1") (pintype "passive"))
      (node (ref "C25") (pin "1") (pinfunction "1_1") (pintype "passive"))
      (node (ref "C26") (pin "1") (pinfunction "1_1") (pintype "passive"))
      (node (ref "C27") (pin "1") (pinfunction "1_1") (pintype "passive"))
      (node (ref "C28") (pin "1") (pinfunction "1_1") (pintype "passive"))
      (node (ref "C29") (pin "1") (pinfunction "1_1") (pintype "passive"))
      (node (ref "C3") (pin "1") (pinfunction "1_1") (pintype "passive"))
      (node (ref "C30") (pin "1") (pinfunction "1_1") (pintype "passive"))
      (node (ref "C31") (pin "1") (pinfunction "1_1") (pintype "passive"))
      (node (ref "C32") (pin "1") (pinfunction "1_1") (pintype "passive"))
      (node (ref "C33") (pin "1") (pinfunction "1_1") (pintype "passive"))
      (node (ref "C34") (pin "1") (pinfunction "1_1") (pintype "passive"))
      (node (ref "C35") (pin "1") (pinfunction "1_1") (pintype "passive"))
      (node (ref "C36") (pin "1") (pinfunction "1_1") (pintype "passive"))
      (node (ref "C37") (pin "1") (pinfunction "1_1") (pintype "passive"))
      (node (ref "C38") (pin "1") (pinfunction "1_1") (pintype "passive"))
      (node (ref "C39") (pin "1") (pinfunction "1_1") (pintype "passive"))
      (node (ref "C4") (pin "1") (pinfunction "1_1") (pintype "passive"))
      (node (ref "C40") (pin "1") (pinfunction "1_1") (pintype "passive"))
      (node (ref "C41") (pin "1") (pinfunction "1_1") (pintype "passive"))
      (node (ref "C42") (pin "+") (pinfunction "+_+") (pintype "passive"))
      (node (ref "C43") (pin "+") (pinfunction "+_+") (pintype "passive"))
      (node (ref "C44") (pin "+") (pinfunction "+_+") (pintype "passive"))
      (node (ref "C45") (pin "+") (pinfunction "+_+") (pintype "passive"))
      (node (ref "C5") (pin "1") (pinfunction "1_1") (pintype "passive"))
      (node (ref "C6") (pin "1") (pinfunction "1_1") (pintype "passive"))
      (node (ref "C7") (pin "1") (pinfunction "1_1") (pintype "passive"))
      (node (ref "C8") (pin "1") (pinfunction "1_1") (pintype "passive"))
      (node (ref "C9") (pin "1") (pinfunction "1_1") (pintype "passive"))
      (node (ref "R1") (pin "2") (pinfunction "2_2") (pintype "passive"))
      (node (ref "R19") (pin "1") (pinfunction "1_1") (pintype "passive"))
      (node (ref "R2") (pin "2") (pinfunction "2_2") (pintype "passive"))
      (node (ref "R20") (pin "2") (pinfunction "2_2") (pintype "passive"))
      (node (ref "R3") (pin "2") (pinfunction "2_2") (pintype "passive"))
      (node (ref "R4") (pin "2") (pinfunction "2_2") (pintype "passive"))
      (node (ref "R5") (pin "2") (pinfunction "2_2") (pintype "passive"))
      (node (ref "R6") (pin "2") (pinfunction "2_2") (pintype "passive"))
      (node (ref "R7") (pin "2") (pinfunction "2_2") (pintype "passive"))
      (node (ref "R8") (pin "2") (pinfunction "2_2") (pintype "passive"))
      (node (ref "R9") (pin "2") (pinfunction "2_2") (pintype "passive"))
      (node (ref "U$2") (pin "AA2") (pinfunction "1_AA2") (pintype "bidirectional"))
      (node (ref "U$2") (pin "BA2") (pinfunction "1_BA2") (pintype "bidirectional"))
      (node (ref "U$2") (pin "CA2") (pinfunction "1_CA2") (pintype "bidirectional"))
    )
    (net (code "121") (name "WRT") (class "Default")
      (node (ref "E10") (pin "5") (pinfunction "I2_5") (pintype "input"))
      (node (ref "E24") (pin "10") (pinfunction "I1_10") (pintype "input"))
      (node (ref "E32") (pin "2") (pinfunction "O_2") (pintype "output"))
      (node (ref "X14") (pin "4") (pinfunction "I0_4") (pintype "input"))
    )
    (net (code "122") (name "XFER_IOT") (class "Default")
      (node (ref "E10") (pin "1") (pinfunction "I0_1") (pintype "input"))
      (node (ref "E12") (pin "12") (pinfunction "I0_12") (pintype "input"))
      (node (ref "E28") (pin "9") (pinfunction "I0_9") (pintype "input"))
      (node (ref "E38") (pin "6") (pinfunction "O_6") (pintype "output"))
    )
    (net (code "123") (name "XFER_REQ") (class "Default")
      (node (ref "E30") (pin "3") (pinfunction "CLK_3") (pintype "input"))
      (node (ref "E36") (pin "4") (pinfunction "A2_4") (pintype "output"))
      (node (ref "E39") (pin "12") (pinfunction "I1_12") (pintype "input"))
    )
    (net (code "124") (name "unconnected-(E4A-QA-Pad14)") (class "Default")
      (node (ref "E4") (pin "14") (pinfunction "QA_14") (pintype "output"))
    )
    (net (code "125") (name "unconnected-(E4A-QB-Pad13)") (class "Default")
      (node (ref "E4") (pin "13") (pinfunction "QB_13") (pintype "output"))
    )
    (net (code "126") (name "unconnected-(E4A-QC-Pad12)") (class "Default")
      (node (ref "E4") (pin "12") (pinfunction "QC_12") (pintype "output"))
    )
    (net (code "127") (name "unconnected-(E4A-QD-Pad11)") (class "Default")
      (node (ref "E4") (pin "11") (pinfunction "QD_11") (pintype "output"))
    )
    (net (code "128") (name "unconnected-(E7A-~{Q}-Pad6)") (class "Default")
      (node (ref "E7") (pin "6") (pinfunction "~{Q}_6") (pintype "output"))
    )
    (net (code "129") (name "unconnected-(E9A-~{QD}-Pad12)") (class "Default")
      (node (ref "E9") (pin "12") (pinfunction "~{QD}_12") (pintype "output"))
    )
    (net (code "130") (name "unconnected-(E15A-~{Q}-Pad6)") (class "Default")
      (node (ref "E15") (pin "6") (pinfunction "~{Q}_6") (pintype "output"))
    )
    (net (code "131") (name "unconnected-(E15B-~{Q}-Pad8)") (class "Default")
      (node (ref "E15") (pin "8") (pinfunction "~{Q}_8") (pintype "output"))
    )
    (net (code "132") (name "unconnected-(E21A-~{QD}-Pad12)") (class "Default")
      (node (ref "E21") (pin "12") (pinfunction "~{QD}_12") (pintype "output"))
    )
    (net (code "133") (name "unconnected-(E22A-~{Q}-Pad6)") (class "Default")
      (node (ref "E22") (pin "6") (pinfunction "~{Q}_6") (pintype "output"))
    )
    (net (code "134") (name "unconnected-(E22B-~{Q}-Pad8)") (class "Default")
      (node (ref "E22") (pin "8") (pinfunction "~{Q}_8") (pintype "output"))
    )
    (net (code "135") (name "unconnected-(E26A-~{Q}-Pad6)") (class "Default")
      (node (ref "E26") (pin "6") (pinfunction "~{Q}_6") (pintype "output"))
    )
    (net (code "136") (name "unconnected-(E26B-~{Q}-Pad8)") (class "Default")
      (node (ref "E26") (pin "8") (pinfunction "~{Q}_8") (pintype "output"))
    )
    (net (code "137") (name "unconnected-(E27A-Q-Pad15)") (class "Default")
      (node (ref "E27") (pin "15") (pinfunction "Q_15") (pintype "output"))
    )
    (net (code "138") (name "unconnected-(E30A-~{Q}-Pad6)") (class "Default")
      (node (ref "E30") (pin "6") (pinfunction "~{Q}_6") (pintype "output"))
    )
    (net (code "139") (name "unconnected-(E30B-~{Q}-Pad8)") (class "Default")
      (node (ref "E30") (pin "8") (pinfunction "~{Q}_8") (pintype "output"))
    )
    (net (code "140") (name "unconnected-(E31-Pad7)") (class "Default")
      (node (ref "E31") (pin "7") (pinfunction "7_7") (pintype "passive"))
    )
    (net (code "141") (name "unconnected-(E31-Pad8)") (class "Default")
      (node (ref "E31") (pin "8") (pinfunction "8_8") (pintype "passive"))
    )
    (net (code "142") (name "unconnected-(E31-Pad9)") (class "Default")
      (node (ref "E31") (pin "9") (pinfunction "9_9") (pintype "passive"))
    )
    (net (code "143") (name "unconnected-(E31-Pad10)") (class "Default")
      (node (ref "E31") (pin "10") (pinfunction "10_10") (pintype "passive"))
    )
    (net (code "144") (name "unconnected-(E33A-~{QD}-Pad12)") (class "Default")
      (node (ref "E33") (pin "12") (pinfunction "~{QD}_12") (pintype "output"))
    )
    (net (code "145") (name "unconnected-(E41A-O0-Pad1)") (class "Default")
      (node (ref "E41") (pin "1") (pinfunction "O0_1") (pintype "output"))
    )
    (net (code "146") (name "unconnected-(E41A-O8-Pad10)") (class "Default")
      (node (ref "E41") (pin "10") (pinfunction "O8_10") (pintype "output"))
    )
    (net (code "147") (name "unconnected-(E41A-O9-Pad11)") (class "Default")
      (node (ref "E41") (pin "11") (pinfunction "O9_11") (pintype "output"))
    )
    (net (code "148") (name "~{BINIT}") (class "Default")
      (node (ref "E15") (pin "1") (pinfunction "CLR_1") (pintype "input"))
      (node (ref "E22") (pin "13") (pinfunction "CLR_13") (pintype "input"))
      (node (ref "E26") (pin "13") (pinfunction "CLR_13") (pintype "input"))
      (node (ref "E30") (pin "13") (pinfunction "CLR_13") (pintype "input"))
      (node (ref "E32") (pin "4") (pinfunction "O_4") (pintype "output"))
    )
    (net (code "149") (name "~{C0}") (class "Default")
      (node (ref "U$2") (pin "CE1") (pinfunction "1_CE1") (pintype "bidirectional"))
      (node (ref "X14") (pin "3") (pinfunction "O_3") (pintype "open_collector"))
    )
    (net (code "150") (name "~{C1}") (class "Default")
      (node (ref "U$2") (pin "CH1") (pinfunction "1_CH1") (pintype "bidirectional"))
      (node (ref "X14") (pin "11") (pinfunction "O_11") (pintype "open_collector"))
    )
    (net (code "151") (name "~{CLK_BUF}") (class "Default")
      (node (ref "E21") (pin "6") (pinfunction "CLK_6") (pintype "input"))
      (node (ref "E33") (pin "6") (pinfunction "CLK_6") (pintype "input"))
      (node (ref "E8") (pin "12") (pinfunction "O_12") (pintype "output"))
      (node (ref "E9") (pin "6") (pinfunction "CLK_6") (pintype "input"))
    )
    (net (code "152") (name "~{CLK_PARITY}") (class "Default")
      (node (ref "E19") (pin "1") (pinfunction "O_1") (pintype "output"))
      (node (ref "E27") (pin "1") (pinfunction "CLK_1") (pintype "input"))
      (node (ref "E8") (pin "3") (pinfunction "I_3") (pintype "input"))
    )
    (net (code "153") (name "~{DATA0}") (class "Default")
      (node (ref "E1") (pin "15") (pinfunction "Y3_15") (pintype "input"))
      (node (ref "U$2") (pin "AR1") (pinfunction "1_AR1") (pintype "bidirectional"))
      (node (ref "X5") (pin "3") (pinfunction "O_3") (pintype "open_collector"))
    )
    (net (code "154") (name "~{DATA1}") (class "Default")
      (node (ref "E1") (pin "13") (pinfunction "Y2_13") (pintype "input"))
      (node (ref "U$2") (pin "AS1") (pinfunction "1_AS1") (pintype "bidirectional"))
      (node (ref "X5") (pin "6") (pinfunction "O_6") (pintype "open_collector"))
    )
    (net (code "155") (name "~{DATA2}") (class "Default")
      (node (ref "E1") (pin "11") (pinfunction "Y1_11") (pintype "input"))
      (node (ref "U$2") (pin "AU1") (pinfunction "1_AU1") (pintype "bidirectional"))
      (node (ref "X5") (pin "8") (pinfunction "O_8") (pintype "open_collector"))
    )
    (net (code "156") (name "~{DATA3}") (class "Default")
      (node (ref "E1") (pin "5") (pinfunction "Y3_5") (pintype "input"))
      (node (ref "U$2") (pin "AV1") (pinfunction "1_AV1") (pintype "bidirectional"))
      (node (ref "X5") (pin "11") (pinfunction "O_11") (pintype "open_collector"))
    )
    (net (code "157") (name "~{DATA4}") (class "Default")
      (node (ref "E1") (pin "3") (pinfunction "Y2_3") (pintype "input"))
      (node (ref "U$2") (pin "BR1") (pinfunction "1_BR1") (pintype "bidirectional"))
      (node (ref "X17") (pin "3") (pinfunction "O_3") (pintype "open_collector"))
    )
    (net (code "158") (name "~{DATA5}") (class "Default")
      (node (ref "E1") (pin "1") (pinfunction "Y1_1") (pintype "input"))
      (node (ref "U$2") (pin "BS1") (pinfunction "1_BS1") (pintype "bidirectional"))
      (node (ref "X17") (pin "6") (pinfunction "O_6") (pintype "open_collector"))
    )
    (net (code "159") (name "~{DATA6}") (class "Default")
      (node (ref "E25") (pin "15") (pinfunction "Y3_15") (pintype "input"))
      (node (ref "U$2") (pin "BU1") (pinfunction "1_BU1") (pintype "bidirectional"))
      (node (ref "X17") (pin "8") (pinfunction "O_8") (pintype "open_collector"))
    )
    (net (code "160") (name "~{DATA7}") (class "Default")
      (node (ref "E25") (pin "13") (pinfunction "Y2_13") (pintype "input"))
      (node (ref "U$2") (pin "BV1") (pinfunction "1_BV1") (pintype "bidirectional"))
      (node (ref "X17") (pin "11") (pinfunction "O_11") (pintype "open_collector"))
    )
    (net (code "161") (name "~{DATA8}") (class "Default")
      (node (ref "E25") (pin "11") (pinfunction "Y1_11") (pintype "input"))
      (node (ref "U$2") (pin "DR1") (pinfunction "1_DR1") (pintype "bidirectional"))
      (node (ref "X29") (pin "3") (pinfunction "O_3") (pintype "open_collector"))
    )
    (net (code "162") (name "~{DATA9}") (class "Default")
      (node (ref "E25") (pin "5") (pinfunction "Y3_5") (pintype "input"))
      (node (ref "U$2") (pin "DS1") (pinfunction "1_DS1") (pintype "bidirectional"))
      (node (ref "X29") (pin "6") (pinfunction "O_6") (pintype "open_collector"))
    )
    (net (code "163") (name "~{DATA10}") (class "Default")
      (node (ref "E25") (pin "3") (pinfunction "Y2_3") (pintype "input"))
      (node (ref "U$2") (pin "DU1") (pinfunction "1_DU1") (pintype "bidirectional"))
      (node (ref "X29") (pin "8") (pinfunction "O_8") (pintype "open_collector"))
    )
    (net (code "164") (name "~{DATA11}") (class "Default")
      (node (ref "E25") (pin "1") (pinfunction "Y1_1") (pintype "input"))
      (node (ref "U$2") (pin "DV1") (pinfunction "1_DV1") (pintype "bidirectional"))
      (node (ref "X29") (pin "11") (pinfunction "O_11") (pintype "open_collector"))
    )
    (net (code "165") (name "~{DONE_SKIP}") (class "Default")
      (node (ref "E10") (pin "11") (pinfunction "I2_11") (pintype "input"))
      (node (ref "E19") (pin "9") (pinfunction "I1_9") (pintype "input"))
      (node (ref "E34") (pin "11") (pinfunction "O_11") (pintype "output"))
      (node (ref "U$2") (pin "CB1") (pinfunction "1_CB1") (pintype "bidirectional"))
    )
    (net (code "166") (name "~{DONE}") (class "Default")
      (node (ref "E10") (pin "4") (pinfunction "I1_4") (pintype "input"))
      (node (ref "E28") (pin "10") (pinfunction "I1_10") (pintype "input"))
      (node (ref "E32") (pin "8") (pinfunction "O_8") (pintype "output"))
    )
    (net (code "167") (name "~{ENB_BUF_LD}") (class "Default")
      (node (ref "E16") (pin "11") (pinfunction "O_11") (pintype "output"))
      (node (ref "E20") (pin "13") (pinfunction "I2_13") (pintype "input"))
      (node (ref "E21") (pin "13") (pinfunction "SHF_13") (pintype "input"))
      (node (ref "E33") (pin "13") (pinfunction "SHF_13") (pintype "input"))
      (node (ref "E4") (pin "9") (pinfunction "LD_9") (pintype "input"))
      (node (ref "E9") (pin "13") (pinfunction "SHF_13") (pintype "input"))
    )
    (net (code "168") (name "~{ERR_SKIP}") (class "Default")
      (node (ref "E10") (pin "10") (pinfunction "I1_10") (pintype "input"))
      (node (ref "E23") (pin "9") (pinfunction "I1_9") (pintype "input"))
      (node (ref "E34") (pin "3") (pinfunction "O_3") (pintype "output"))
    )
    (net (code "169") (name "~{INIT_IOT}") (class "Default")
      (node (ref "E41") (pin "9") (pinfunction "O7_9") (pintype "output"))
      (node (ref "E7") (pin "2") (pinfunction "D_2") (pintype "input"))
    )
    (net (code "170") (name "~{INIT}") (class "Default")
      (node (ref "E16") (pin "10") (pinfunction "I1_10") (pintype "input"))
      (node (ref "E2") (pin "1") (pinfunction "CLR_1") (pintype "input"))
      (node (ref "E2") (pin "13") (pinfunction "CLR_13") (pintype "input"))
      (node (ref "E21") (pin "1") (pinfunction "CLR_1") (pintype "input"))
      (node (ref "E33") (pin "1") (pinfunction "CLR_1") (pintype "input"))
      (node (ref "E4") (pin "1") (pinfunction "CLR_1") (pintype "input"))
      (node (ref "E8") (pin "6") (pinfunction "O_6") (pintype "output"))
      (node (ref "E9") (pin "1") (pinfunction "CLR_1") (pintype "input"))
    )
    (net (code "171") (name "~{INTERNAL_IO}") (class "Default")
      (node (ref "E18X") (pin "3") (pinfunction "O_3") (pintype "open_collector"))
      (node (ref "U$2") (pin "CL1") (pinfunction "1_CL1") (pintype "bidirectional"))
    )
    (net (code "172") (name "~{INTR_IOT}") (class "Default")
      (node (ref "E41") (pin "7") (pinfunction "O6_7") (pintype "output"))
      (node (ref "E6") (pin "6") (pinfunction "I1_6") (pintype "input"))
    )
    (net (code "173") (name "~{INT_RQST}") (class "Default")
      (node (ref "E18X") (pin "6") (pinfunction "O_6") (pintype "open_collector"))
      (node (ref "U$2") (pin "CP1") (pinfunction "1_CP1") (pintype "bidirectional"))
    )
    (net (code "174") (name "~{IO_PAUSE}") (class "Default")
      (node (ref "E39") (pin "6") (pinfunction "I0_6") (pintype "input"))
      (node (ref "U$2") (pin "CD1") (pinfunction "1_CD1") (pintype "bidirectional"))
    )
    (net (code "175") (name "~{LCD_IOT}") (class "Default")
      (node (ref "E12") (pin "4") (pinfunction "I0_4") (pintype "input"))
      (node (ref "E16") (pin "5") (pinfunction "I1_5") (pintype "input"))
      (node (ref "E38") (pin "3") (pinfunction "I_3") (pintype "input"))
      (node (ref "E41") (pin "2") (pinfunction "O1_2") (pintype "output"))
      (node (ref "E6") (pin "3") (pinfunction "I1_3") (pintype "input"))
    )
    (net (code "176") (name "~{MAINT}") (class "Default")
      (node (ref "E10") (pin "3") (pinfunction "I0_3") (pintype "input"))
      (node (ref "E16") (pin "12") (pinfunction "I0_12") (pintype "input"))
      (node (ref "E2") (pin "8") (pinfunction "~{Q}_8") (pintype "output"))
      (node (ref "E22") (pin "4") (pinfunction "PRE_4") (pintype "input"))
      (node (ref "E26") (pin "4") (pinfunction "PRE_4") (pintype "input"))
      (node (ref "E28") (pin "1") (pinfunction "I0_1") (pintype "input"))
      (node (ref "E28") (pin "12") (pinfunction "I2_12") (pintype "input"))
      (node (ref "E30") (pin "4") (pinfunction "PRE_4") (pintype "input"))
      (node (ref "E32") (pin "11") (pinfunction "I_11") (pintype "input"))
    )
    (net (code "177") (name "~{MD03}") (class "Default")
      (node (ref "E35") (pin "4") (pinfunction "I0_4") (pintype "input"))
      (node (ref "U$2") (pin "AP1") (pinfunction "1_AP1") (pintype "bidirectional"))
    )
    (net (code "178") (name "~{MD04}") (class "Default")
      (node (ref "E35") (pin "6") (pinfunction "I2_6") (pintype "input"))
      (node (ref "U$2") (pin "BK1") (pinfunction "1_BK1") (pintype "bidirectional"))
    )
    (net (code "179") (name "~{MD05}") (class "Default")
      (node (ref "E35") (pin "5") (pinfunction "I1_5") (pintype "input"))
      (node (ref "U$2") (pin "BL1") (pinfunction "1_BL1") (pintype "bidirectional"))
    )
    (net (code "180") (name "~{MD06}") (class "Default")
      (node (ref "E31") (pin "4") (pinfunction "4_4") (pintype "passive"))
      (node (ref "E40") (pin "1") (pinfunction "Y1_1") (pintype "input"))
      (node (ref "U$2") (pin "BM1") (pinfunction "1_BM1") (pintype "bidirectional"))
    )
    (net (code "181") (name "~{MD07}") (class "Default")
      (node (ref "E31") (pin "5") (pinfunction "5_5") (pintype "passive"))
      (node (ref "E40") (pin "3") (pinfunction "Y2_3") (pintype "input"))
      (node (ref "U$2") (pin "BP1") (pinfunction "1_BP1") (pintype "bidirectional"))
    )
    (net (code "182") (name "~{MD08}") (class "Default")
      (node (ref "E31") (pin "6") (pinfunction "6_6") (pintype "passive"))
      (node (ref "E40") (pin "5") (pinfunction "Y3_5") (pintype "input"))
      (node (ref "U$2") (pin "DK1") (pinfunction "1_DK1") (pintype "bidirectional"))
    )
    (net (code "183") (name "~{MD09}") (class "Default")
      (node (ref "E40") (pin "15") (pinfunction "Y3_15") (pintype "input"))
      (node (ref "U$2") (pin "DL1") (pinfunction "1_DL1") (pintype "bidirectional"))
    )
    (net (code "184") (name "~{MD10}") (class "Default")
      (node (ref "E40") (pin "13") (pinfunction "Y2_13") (pintype "input"))
      (node (ref "U$2") (pin "DM1") (pinfunction "1_DM1") (pintype "bidirectional"))
    )
    (net (code "185") (name "~{MD11}") (class "Default")
      (node (ref "E40") (pin "11") (pinfunction "Y1_11") (pintype "input"))
      (node (ref "U$2") (pin "DP1") (pinfunction "1_DP1") (pintype "bidirectional"))
    )
    (net (code "186") (name "~{PARITY}") (class "Default")
      (node (ref "E24") (pin "12") (pinfunction "I0_12") (pintype "input"))
      (node (ref "E27") (pin "14") (pinfunction "~{Q}_14") (pintype "output"))
    )
    (net (code "187") (name "~{RX8_SEL}") (class "Default")
      (node (ref "E1") (pin "7") (pinfunction "FORCE0_7") (pintype "input"))
      (node (ref "E1") (pin "9") (pinfunction "FORCE0_9") (pintype "input"))
      (node (ref "E25") (pin "7") (pinfunction "FORCE0_7") (pintype "input"))
      (node (ref "E25") (pin "9") (pinfunction "FORCE0_9") (pintype "input"))
      (node (ref "E32") (pin "6") (pinfunction "O_6") (pintype "output"))
    )
    (net (code "188") (name "~{RX_12_BIT}") (class "Default")
      (node (ref "DRIVE") (pin "FF") (pinfunction "28_FF") (pintype "bidirectional"))
      (node (ref "R16") (pin "2") (pinfunction "2_2") (pintype "passive"))
      (node (ref "R7") (pin "1") (pinfunction "1_1") (pintype "passive"))
      (node (ref "X14") (pin "8") (pinfunction "O_8") (pintype "open_collector"))
    )
    (net (code "189") (name "~{RX_DATA}") (class "Default")
      (node (ref "DRIVE") (pin "BB") (pinfunction "24_BB") (pintype "bidirectional"))
      (node (ref "E36") (pin "11") (pinfunction "Y1_11") (pintype "input"))
      (node (ref "R17") (pin "2") (pinfunction "2_2") (pintype "passive"))
      (node (ref "R8") (pin "1") (pinfunction "1_1") (pintype "passive"))
      (node (ref "X14") (pin "6") (pinfunction "O_6") (pintype "open_collector"))
    )
    (net (code "190") (name "~{RX_DONE}") (class "Default")
      (node (ref "DRIVE") (pin "X") (pinfunction "20_X") (pintype "bidirectional"))
      (node (ref "E36") (pin "5") (pinfunction "Y3_5") (pintype "input"))
      (node (ref "R13") (pin "2") (pinfunction "2_2") (pintype "passive"))
      (node (ref "R4") (pin "1") (pinfunction "1_1") (pintype "passive"))
    )
    (net (code "191") (name "~{RX_ERROR}") (class "Default")
      (node (ref "DRIVE") (pin "J") (pinfunction "8_J") (pintype "bidirectional"))
      (node (ref "E36") (pin "1") (pinfunction "Y1_1") (pintype "input"))
      (node (ref "R14") (pin "2") (pinfunction "2_2") (pintype "passive"))
      (node (ref "R5") (pin "1") (pinfunction "1_1") (pintype "passive"))
    )
    (net (code "192") (name "~{RX_INIT}") (class "Default")
      (node (ref "DRIVE") (pin "N") (pinfunction "12_N") (pintype "bidirectional"))
      (node (ref "R9") (pin "1") (pinfunction "1_1") (pintype "passive"))
      (node (ref "X37") (pin "11") (pinfunction "O_11") (pintype "open_collector"))
    )
    (net (code "193") (name "~{RX_OUT}") (class "Default")
      (node (ref "DRIVE") (pin "RR") (pinfunction "36_RR") (pintype "bidirectional"))
      (node (ref "E36") (pin "15") (pinfunction "Y3_15") (pintype "input"))
      (node (ref "R12") (pin "2") (pinfunction "2_2") (pintype "passive"))
      (node (ref "R3") (pin "1") (pinfunction "1_1") (pintype "passive"))
    )
    (net (code "194") (name "~{RX_RUN}") (class "Default")
      (node (ref "DRIVE") (pin "D") (pinfunction "4_D") (pintype "bidirectional"))
      (node (ref "E18X") (pin "11") (pinfunction "O_11") (pintype "open_collector"))
      (node (ref "R15") (pin "2") (pinfunction "2_2") (pintype "passive"))
      (node (ref "R6") (pin "1") (pinfunction "1_1") (pintype "passive"))
    )
    (net (code "195") (name "~{RX_SHIFT}") (class "Default")
      (node (ref "DRIVE") (pin "LL") (pinfunction "32_LL") (pintype "bidirectional"))
      (node (ref "E36") (pin "13") (pinfunction "Y2_13") (pintype "input"))
      (node (ref "R10") (pin "2") (pinfunction "2_2") (pintype "passive"))
      (node (ref "R2") (pin "1") (pinfunction "1_1") (pintype "passive"))
    )
    (net (code "196") (name "~{RX_TR_REQ}") (class "Default")
      (node (ref "DRIVE") (pin "T") (pinfunction "16_T") (pintype "bidirectional"))
      (node (ref "E36") (pin "3") (pinfunction "Y2_3") (pintype "input"))
      (node (ref "R1") (pin "1") (pinfunction "1_1") (pintype "passive"))
      (node (ref "R11") (pin "2") (pinfunction "2_2") (pintype "passive"))
    )
    (net (code "197") (name "~{SDN_IOT}") (class "Default")
      (node (ref "E38") (pin "11") (pinfunction "I_11") (pintype "input"))
      (node (ref "E41") (pin "6") (pinfunction "O5_6") (pintype "output"))
    )
    (net (code "198") (name "~{SER_IOT}") (class "Default")
      (node (ref "E38") (pin "9") (pinfunction "I_9") (pintype "input"))
      (node (ref "E41") (pin "5") (pinfunction "O4_5") (pintype "output"))
    )
    (net (code "199") (name "~{SKIP}") (class "Default")
      (node (ref "E18X") (pin "8") (pinfunction "O_8") (pintype "open_collector"))
      (node (ref "U$2") (pin "CS1") (pinfunction "1_CS1") (pintype "bidirectional"))
    )
    (net (code "200") (name "~{STR_IOT}") (class "Default")
      (node (ref "E38") (pin "13") (pinfunction "I_13") (pintype "input"))
      (node (ref "E41") (pin "4") (pinfunction "O3_4") (pintype "output"))
    )
    (net (code "201") (name "~{TP3}") (class "Default")
      (node (ref "E11") (pin "14") (pinfunction "O_14") (pintype "output"))
      (node (ref "E19") (pin "8") (pinfunction "I0_8") (pintype "input"))
      (node (ref "E20") (pin "1") (pinfunction "I0_1") (pintype "input"))
      (node (ref "E23") (pin "11") (pinfunction "I0_11") (pintype "input"))
      (node (ref "E23") (pin "8") (pinfunction "I0_8") (pintype "input"))
      (node (ref "E32") (pin "13") (pinfunction "I_13") (pintype "input"))
      (node (ref "E6") (pin "2") (pinfunction "I0_2") (pintype "input"))
      (node (ref "E6") (pin "5") (pinfunction "I0_5") (pintype "input"))
    )
    (net (code "202") (name "~{TR_SKIP}") (class "Default")
      (node (ref "E10") (pin "9") (pinfunction "I0_9") (pintype "input"))
      (node (ref "E23") (pin "12") (pinfunction "I1_12") (pintype "input"))
      (node (ref "E34") (pin "8") (pinfunction "O_8") (pintype "output"))
      (node (ref "U$2") (pin "DB1") (pinfunction "1_DB1") (pintype "bidirectional"))
    )
    (net (code "203") (name "~{XFER_IOT}") (class "Default")
      (node (ref "E16") (pin "4") (pinfunction "I0_4") (pintype "input"))
      (node (ref "E19") (pin "12") (pinfunction "I1_12") (pintype "input"))
      (node (ref "E38") (pin "5") (pinfunction "I_5") (pintype "input"))
      (node (ref "E41") (pin "3") (pinfunction "O2_3") (pintype "output"))
    )
  )
)
